# MBot.net
KiCad netlist of a schematic drawn in EAGLE
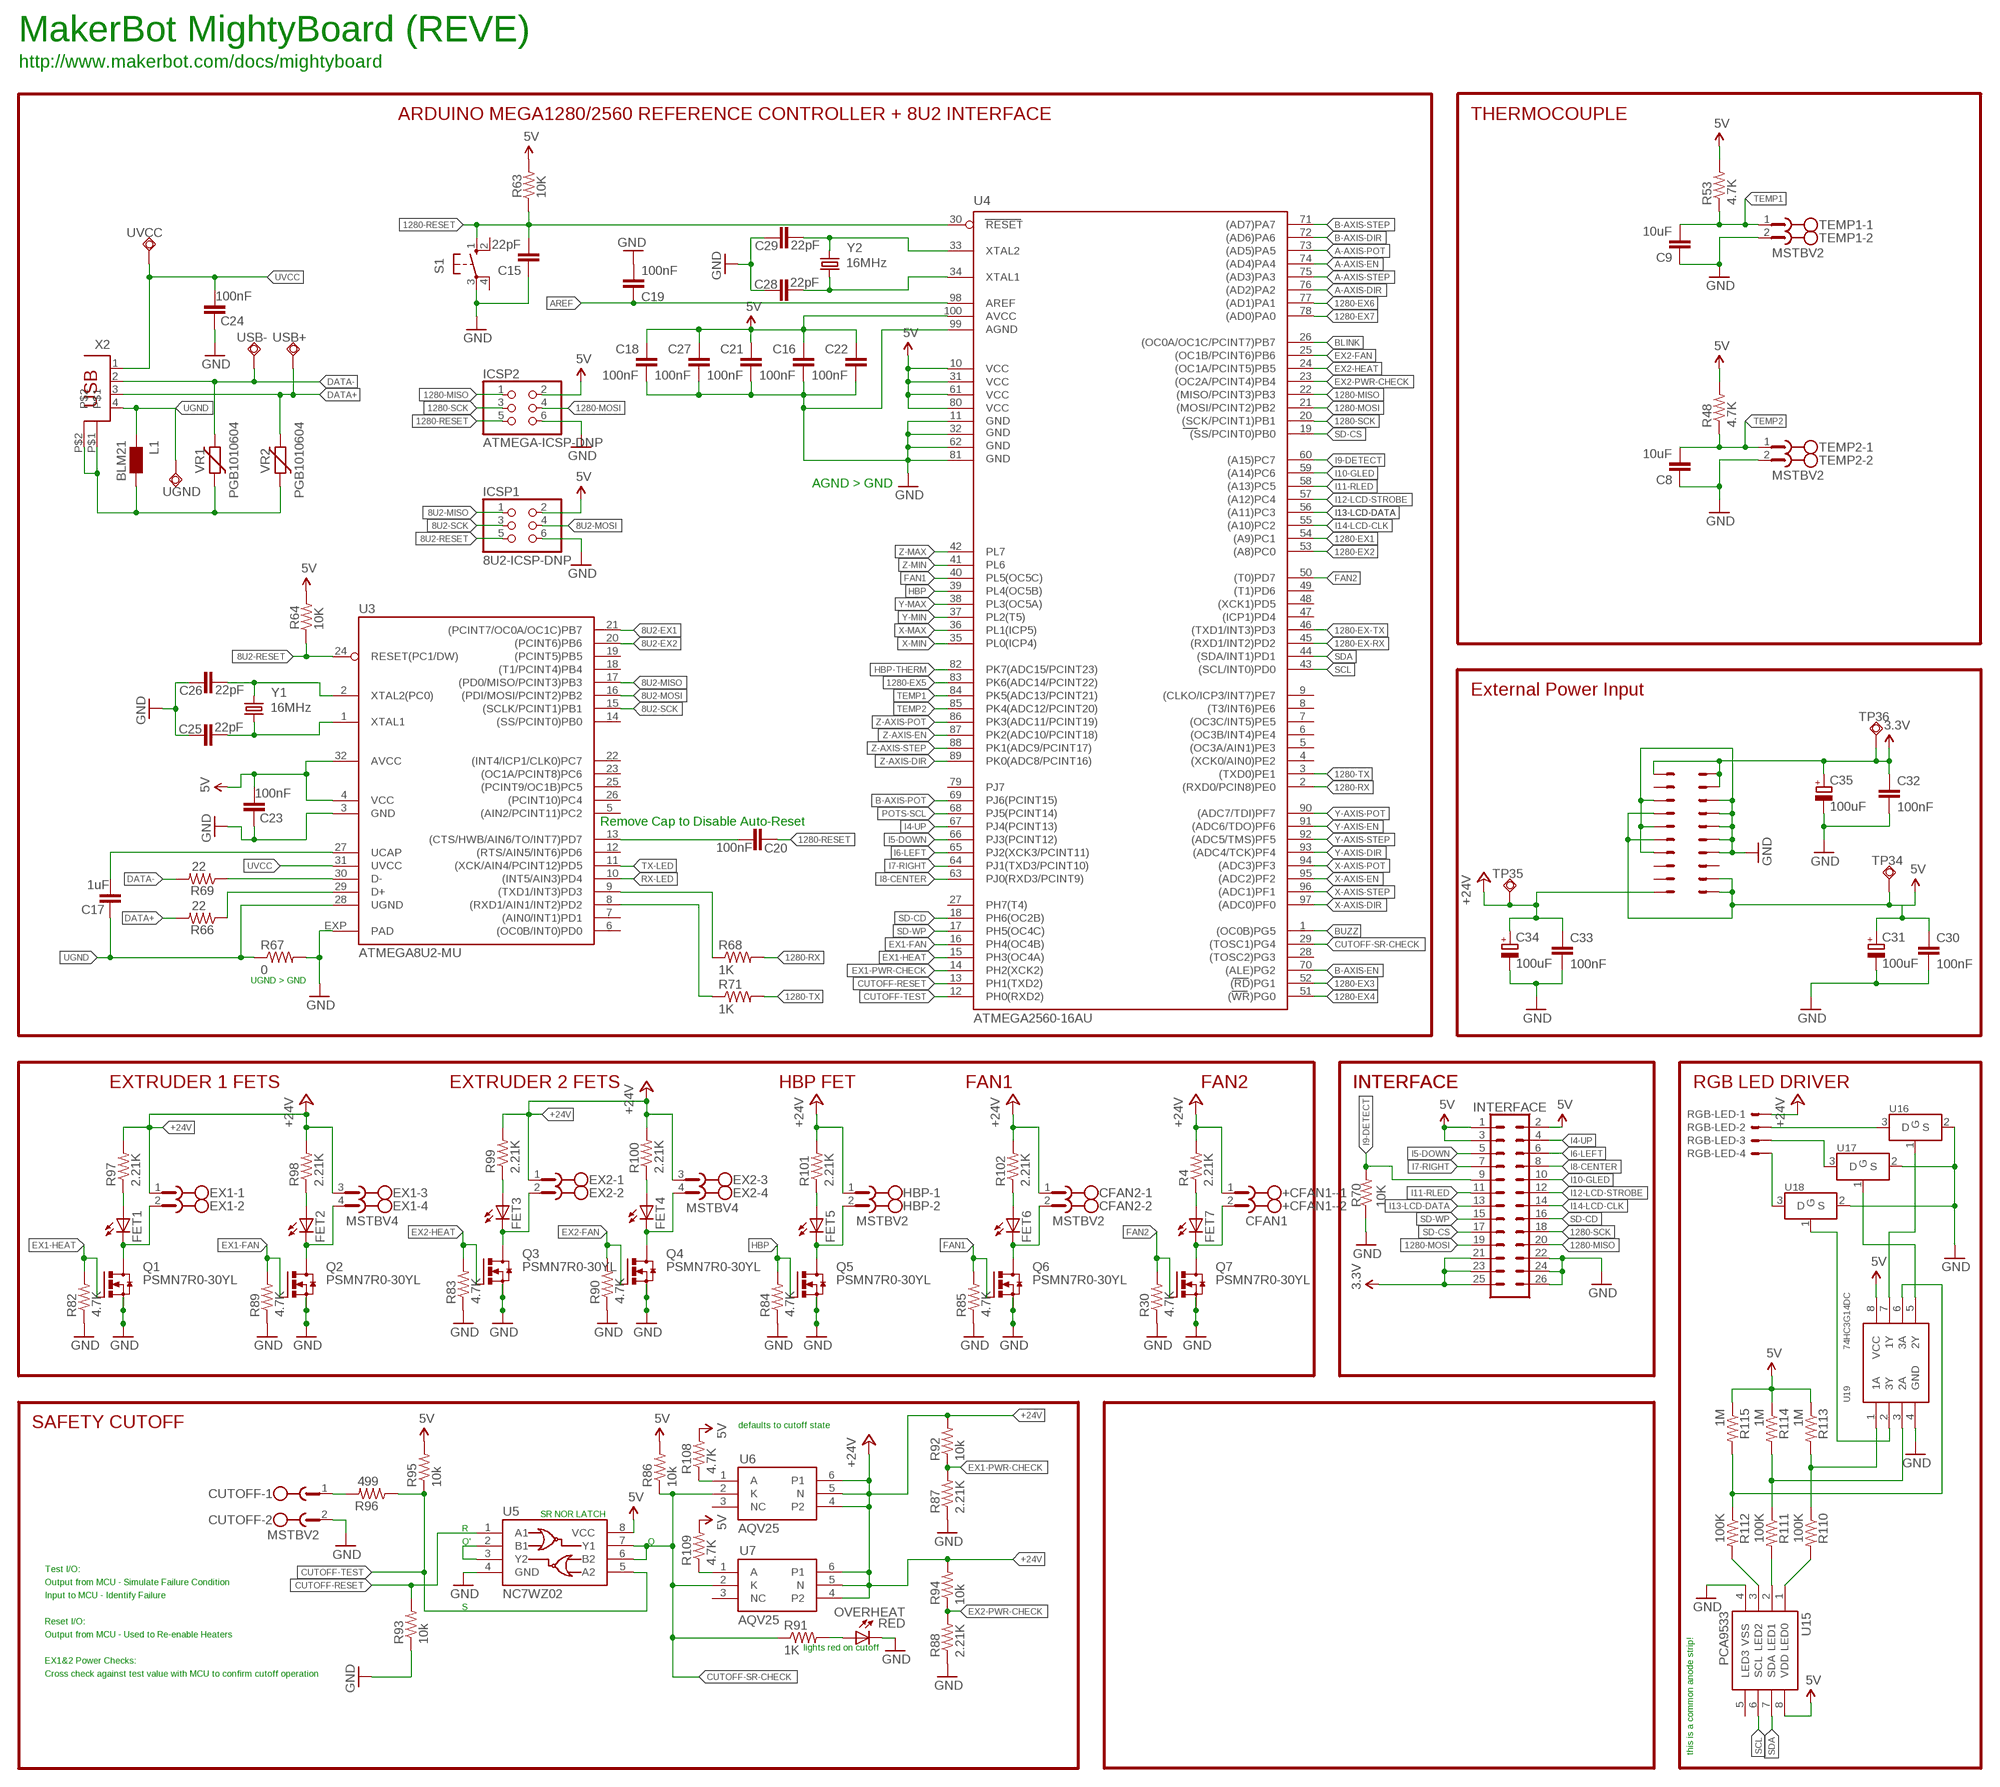
[diagram p0: schematic, sheet 1, part 1 of 2]
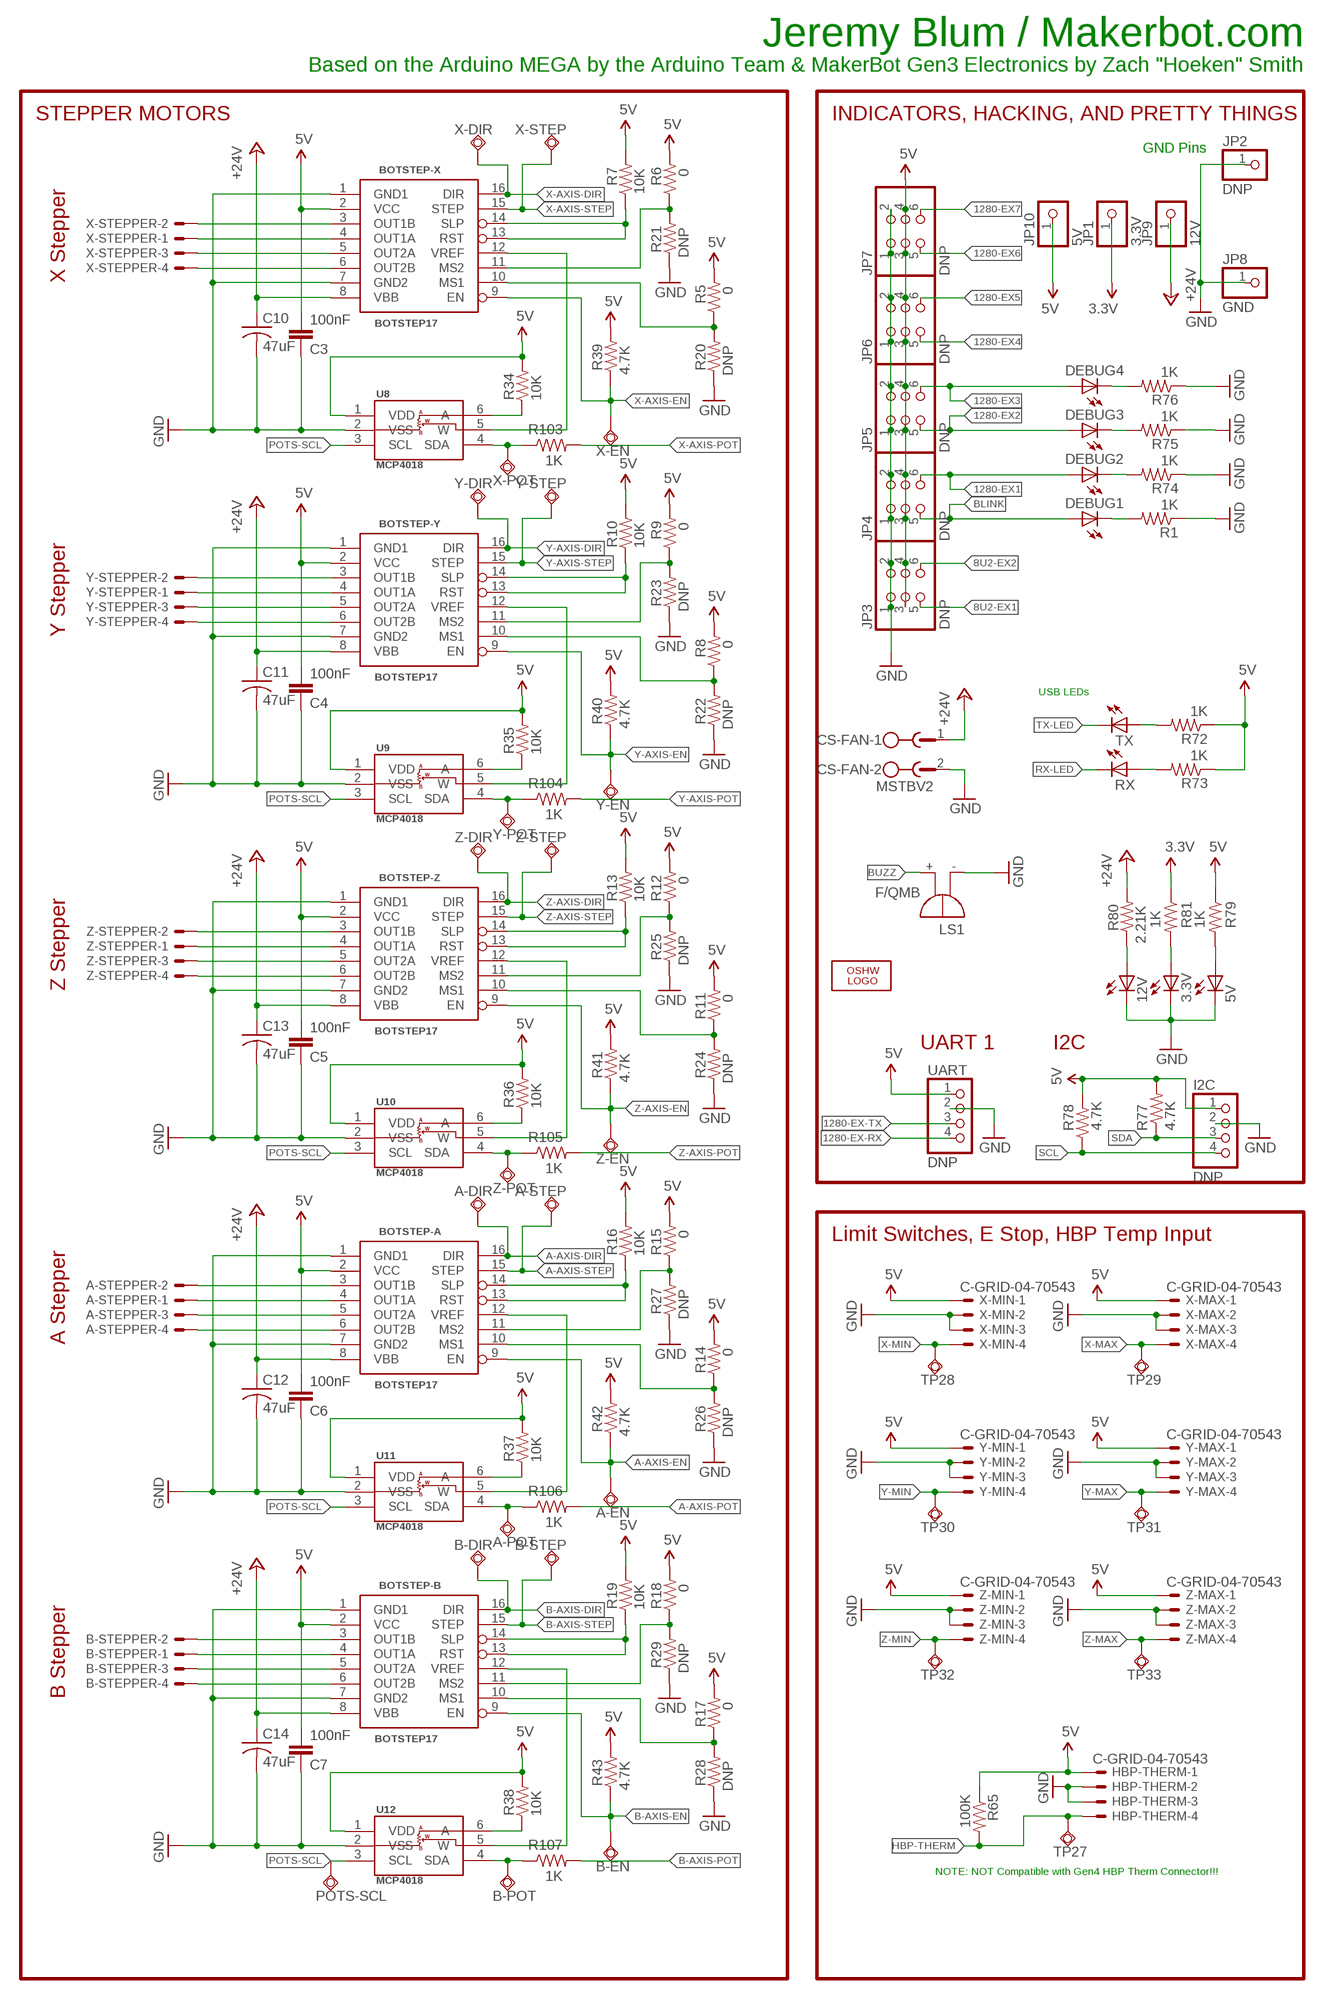
[diagram p1: schematic, sheet 1, part 2 of 2]

(export (version "E")
  (design (tool "Eeschema 10.0.6"))
  (components
    (comp (ref "+CFAN1-")
      (value "CFAN1")
      (footprint "eagle-import:MSTBV2")
      (fields (field (name "MPN") "MSTBV 2,5/2-GF-5.08"))
      (libsource (lib "eagle-import") (part "MSTBV2"))
    )
    (comp (ref "3.3V")
      (value "GREEN")
      (footprint "eagle-import:LED-0805")
      (libsource (lib "eagle-import") (part "LED0805"))
    )
    (comp (ref "5V")
      (value "GREEN")
      (footprint "eagle-import:LED-0805")
      (libsource (lib "eagle-import") (part "LED0805"))
    )
    (comp (ref "12V")
      (value "GREEN")
      (footprint "eagle-import:LED-0805")
      (libsource (lib "eagle-import") (part "LED0805"))
    )
    (comp (ref "A-DIR")
      (value "TPSQTP09R")
      (footprint "eagle-import:TP09R")
      (libsource (lib "eagle-import") (part "TPSQTP09R"))
    )
    (comp (ref "A-EN")
      (value "TPSQTP09R")
      (footprint "eagle-import:TP09R")
      (libsource (lib "eagle-import") (part "TPSQTP09R"))
    )
    (comp (ref "A-POT")
      (value "TPSQTP09R")
      (footprint "eagle-import:TP09R")
      (libsource (lib "eagle-import") (part "TPSQTP09R"))
    )
    (comp (ref "A-STEP")
      (value "TPSQTP09R")
      (footprint "eagle-import:TP09R")
      (libsource (lib "eagle-import") (part "TPSQTP09R"))
    )
    (comp (ref "A-STEPPER")
      (value "KK-156-4")
      (footprint "eagle-import:KK-156-4")
      (libsource (lib "eagle-import") (part "KK-156-4"))
    )
    (comp (ref "B-DIR")
      (value "TPSQTP09R")
      (footprint "eagle-import:TP09R")
      (libsource (lib "eagle-import") (part "TPSQTP09R"))
    )
    (comp (ref "B-EN")
      (value "TPSQTP09R")
      (footprint "eagle-import:TP09R")
      (libsource (lib "eagle-import") (part "TPSQTP09R"))
    )
    (comp (ref "B-POT")
      (value "TPSQTP09R")
      (footprint "eagle-import:TP09R")
      (libsource (lib "eagle-import") (part "TPSQTP09R"))
    )
    (comp (ref "B-STEP")
      (value "TPSQTP09R")
      (footprint "eagle-import:TP09R")
      (libsource (lib "eagle-import") (part "TPSQTP09R"))
    )
    (comp (ref "B-STEPPER")
      (value "KK-156-4")
      (footprint "eagle-import:KK-156-4")
      (libsource (lib "eagle-import") (part "KK-156-4"))
    )
    (comp (ref "BOTSTEP-A")
      (value "BOTSTEP17")
      (footprint "eagle-import:BOTSTEP17-INV")
      (libsource (lib "eagle-import") (part "BOTSTEP17CHIP-DOWN"))
    )
    (comp (ref "BOTSTEP-B")
      (value "BOTSTEP17")
      (footprint "eagle-import:BOTSTEP17-INV")
      (libsource (lib "eagle-import") (part "BOTSTEP17CHIP-DOWN"))
    )
    (comp (ref "BOTSTEP-X")
      (value "BOTSTEP17")
      (footprint "eagle-import:BOTSTEP17-INV")
      (libsource (lib "eagle-import") (part "BOTSTEP17CHIP-DOWN"))
    )
    (comp (ref "BOTSTEP-Y")
      (value "BOTSTEP17")
      (footprint "eagle-import:BOTSTEP17-INV")
      (libsource (lib "eagle-import") (part "BOTSTEP17CHIP-DOWN"))
    )
    (comp (ref "BOTSTEP-Z")
      (value "BOTSTEP17")
      (footprint "eagle-import:BOTSTEP17-INV")
      (libsource (lib "eagle-import") (part "BOTSTEP17CHIP-DOWN"))
    )
    (comp (ref "C3")
      (value "100nF")
      (footprint "eagle-import:0805")
      (libsource (lib "eagle-import") (part "CAP0805"))
    )
    (comp (ref "C4")
      (value "100nF")
      (footprint "eagle-import:0805")
      (libsource (lib "eagle-import") (part "CAP0805"))
    )
    (comp (ref "C5")
      (value "100nF")
      (footprint "eagle-import:0805")
      (libsource (lib "eagle-import") (part "CAP0805"))
    )
    (comp (ref "C6")
      (value "100nF")
      (footprint "eagle-import:0805")
      (libsource (lib "eagle-import") (part "CAP0805"))
    )
    (comp (ref "C7")
      (value "100nF")
      (footprint "eagle-import:0805")
      (libsource (lib "eagle-import") (part "CAP0805"))
    )
    (comp (ref "C8")
      (value "10uF")
      (footprint "eagle-import:0805")
      (libsource (lib "eagle-import") (part "CAP0805"))
    )
    (comp (ref "C9")
      (value "10uF")
      (footprint "eagle-import:0805")
      (libsource (lib "eagle-import") (part "CAP0805"))
    )
    (comp (ref "C10")
      (value "47uF")
      (footprint "eagle-import:CAP2917")
      (libsource (lib "eagle-import") (part "C-US"))
    )
    (comp (ref "C11")
      (value "47uF")
      (footprint "eagle-import:CAP2917")
      (libsource (lib "eagle-import") (part "C-US"))
    )
    (comp (ref "C12")
      (value "47uF")
      (footprint "eagle-import:CAP2917")
      (libsource (lib "eagle-import") (part "C-US"))
    )
    (comp (ref "C13")
      (value "47uF")
      (footprint "eagle-import:CAP2917")
      (libsource (lib "eagle-import") (part "C-US"))
    )
    (comp (ref "C14")
      (value "47uF")
      (footprint "eagle-import:CAP2917")
      (libsource (lib "eagle-import") (part "C-US"))
    )
    (comp (ref "C15")
      (value "22pF")
      (footprint "eagle-import:0805")
      (libsource (lib "eagle-import") (part "CAP0805"))
    )
    (comp (ref "C16")
      (value "100nF")
      (footprint "eagle-import:0805")
      (libsource (lib "eagle-import") (part "CAP0805"))
    )
    (comp (ref "C17")
      (value "1uF")
      (footprint "eagle-import:0805")
      (libsource (lib "eagle-import") (part "CAP0805"))
    )
    (comp (ref "C18")
      (value "100nF")
      (footprint "eagle-import:0805")
      (libsource (lib "eagle-import") (part "CAP0805"))
    )
    (comp (ref "C19")
      (value "100nF")
      (footprint "eagle-import:0805")
      (libsource (lib "eagle-import") (part "CAP0805"))
    )
    (comp (ref "C20")
      (value "100nF")
      (footprint "eagle-import:0805")
      (libsource (lib "eagle-import") (part "CAP0805"))
    )
    (comp (ref "C21")
      (value "100nF")
      (footprint "eagle-import:0805")
      (libsource (lib "eagle-import") (part "CAP0805"))
    )
    (comp (ref "C22")
      (value "100nF")
      (footprint "eagle-import:0805")
      (libsource (lib "eagle-import") (part "CAP0805"))
    )
    (comp (ref "C23")
      (value "100nF")
      (footprint "eagle-import:0805")
      (libsource (lib "eagle-import") (part "CAP0805"))
    )
    (comp (ref "C24")
      (value "100nF")
      (footprint "eagle-import:0805")
      (libsource (lib "eagle-import") (part "CAP0805"))
    )
    (comp (ref "C25")
      (value "22pF")
      (footprint "eagle-import:0805")
      (libsource (lib "eagle-import") (part "CAP0805"))
    )
    (comp (ref "C26")
      (value "22pF")
      (footprint "eagle-import:0805")
      (libsource (lib "eagle-import") (part "CAP0805"))
    )
    (comp (ref "C27")
      (value "100nF")
      (footprint "eagle-import:0805")
      (libsource (lib "eagle-import") (part "CAP0805"))
    )
    (comp (ref "C28")
      (value "22pF")
      (footprint "eagle-import:0805")
      (libsource (lib "eagle-import") (part "CAP0805"))
    )
    (comp (ref "C29")
      (value "22pF")
      (footprint "eagle-import:0805")
      (libsource (lib "eagle-import") (part "CAP0805"))
    )
    (comp (ref "C30")
      (value "100nF")
      (footprint "eagle-import:0805")
      (libsource (lib "eagle-import") (part "CAP0805"))
    )
    (comp (ref "C31")
      (value "100uF")
      (footprint "eagle-import:E3,5-8")
      (libsource (lib "eagle-import") (part "CPOL-EUE3.5-8"))
    )
    (comp (ref "C32")
      (value "100nF")
      (footprint "eagle-import:0805")
      (libsource (lib "eagle-import") (part "CAP0805"))
    )
    (comp (ref "C33")
      (value "100nF")
      (footprint "eagle-import:0805")
      (libsource (lib "eagle-import") (part "CAP0805"))
    )
    (comp (ref "C34")
      (value "100uF")
      (footprint "eagle-import:E3,5-8")
      (libsource (lib "eagle-import") (part "CPOL-EUE3.5-8"))
    )
    (comp (ref "C35")
      (value "100uF")
      (footprint "eagle-import:E3,5-8")
      (libsource (lib "eagle-import") (part "CPOL-EUE3.5-8"))
    )
    (comp (ref "CFAN2")
      (value "MSTBV2")
      (footprint "eagle-import:MSTBV2")
      (fields (field (name "MPN") "MSTBV 2,5/2-GF-5.08"))
      (libsource (lib "eagle-import") (part "MSTBV2"))
    )
    (comp (ref "CS-FAN")
      (value "MSTBV2")
      (footprint "eagle-import:MSTBV2")
      (fields (field (name "MPN") "MSTBV 2,5/2-GF-5.08"))
      (libsource (lib "eagle-import") (part "MSTBV2"))
    )
    (comp (ref "CUTOFF")
      (value "MSTBV2")
      (footprint "eagle-import:MSTBV2")
      (fields (field (name "MPN") "MSTBV 2,5/2-GF-5.08"))
      (libsource (lib "eagle-import") (part "MSTBV2"))
    )
    (comp (ref "DEBUG1")
      (value "GREEN")
      (footprint "eagle-import:LED-0805")
      (libsource (lib "eagle-import") (part "LED0805"))
    )
    (comp (ref "DEBUG2")
      (value "GREEN")
      (footprint "eagle-import:LED-0805")
      (libsource (lib "eagle-import") (part "LED0805"))
    )
    (comp (ref "DEBUG3")
      (value "GREEN")
      (footprint "eagle-import:LED-0805")
      (libsource (lib "eagle-import") (part "LED0805"))
    )
    (comp (ref "DEBUG4")
      (value "GREEN")
      (footprint "eagle-import:LED-0805")
      (libsource (lib "eagle-import") (part "LED0805"))
    )
    (comp (ref "EX1")
      (value "MSTBV4")
      (footprint "eagle-import:MSTBV4")
      (fields (field (name "MPN") "MSTBV 2,5/4-GF-5.08"))
      (libsource (lib "eagle-import") (part "MSTBV4"))
    )
    (comp (ref "EX2")
      (value "MSTBV4")
      (footprint "eagle-import:MSTBV4")
      (fields (field (name "MPN") "MSTBV 2,5/4-GF-5.08"))
      (libsource (lib "eagle-import") (part "MSTBV4"))
    )
    (comp (ref "FET1")
      (value "GREEN")
      (footprint "eagle-import:LED-0805")
      (libsource (lib "eagle-import") (part "LED0805"))
    )
    (comp (ref "FET2")
      (value "GREEN")
      (footprint "eagle-import:LED-0805")
      (libsource (lib "eagle-import") (part "LED0805"))
    )
    (comp (ref "FET3")
      (value "GREEN")
      (footprint "eagle-import:LED-0805")
      (libsource (lib "eagle-import") (part "LED0805"))
    )
    (comp (ref "FET4")
      (value "GREEN")
      (footprint "eagle-import:LED-0805")
      (libsource (lib "eagle-import") (part "LED0805"))
    )
    (comp (ref "FET5")
      (value "GREEN")
      (footprint "eagle-import:LED-0805")
      (libsource (lib "eagle-import") (part "LED0805"))
    )
    (comp (ref "FET6")
      (value "GREEN")
      (footprint "eagle-import:LED-0805")
      (libsource (lib "eagle-import") (part "LED0805"))
    )
    (comp (ref "FET7")
      (value "GREEN")
      (footprint "eagle-import:LED-0805")
      (libsource (lib "eagle-import") (part "LED0805"))
    )
    (comp (ref "HBP")
      (value "MSTBV2")
      (footprint "eagle-import:MSTBV2")
      (fields (field (name "MPN") "MSTBV 2,5/2-GF-5.08"))
      (libsource (lib "eagle-import") (part "MSTBV2"))
    )
    (comp (ref "HBP-THERM")
      (value "C-GRID-04-70543")
      (footprint "eagle-import:70543-04")
      (libsource (lib "eagle-import") (part "C-GRID-04-70543"))
    )
    (comp (ref "I2C")
      (value "DNP")
      (footprint "eagle-import:1X04")
      (libsource (lib "eagle-import") (part "PINHD-1X4"))
    )
    (comp (ref "ICSP1")
      (value "8U2-ICSP-DNP")
      (footprint "eagle-import:2X03")
      (libsource (lib "eagle-import") (part "PINHD-2X3"))
    )
    (comp (ref "ICSP2")
      (value "ATMEGA-ICSP-DNP")
      (footprint "eagle-import:2X03")
      (libsource (lib "eagle-import") (part "PINHD-2X3"))
    )
    (comp (ref "INTERFACE")
      (value "ML26")
      (footprint "eagle-import:ML26")
      (libsource (lib "eagle-import") (part "ML26"))
    )
    (comp (ref "JP1")
      (value "3.3V")
      (footprint "eagle-import:1X01")
      (libsource (lib "eagle-import") (part "PINHD-1X1"))
    )
    (comp (ref "JP2")
      (value "DNP")
      (footprint "eagle-import:1X01")
      (libsource (lib "eagle-import") (part "PINHD-1X1"))
    )
    (comp (ref "JP3")
      (value "DNP")
      (footprint "eagle-import:2X03")
      (libsource (lib "eagle-import") (part "PINHD-2X3"))
    )
    (comp (ref "JP4")
      (value "DNP")
      (footprint "eagle-import:2X03")
      (libsource (lib "eagle-import") (part "PINHD-2X3"))
    )
    (comp (ref "JP5")
      (value "DNP")
      (footprint "eagle-import:2X03")
      (libsource (lib "eagle-import") (part "PINHD-2X3"))
    )
    (comp (ref "JP6")
      (value "DNP")
      (footprint "eagle-import:2X03")
      (libsource (lib "eagle-import") (part "PINHD-2X3"))
    )
    (comp (ref "JP7")
      (value "DNP")
      (footprint "eagle-import:2X03")
      (libsource (lib "eagle-import") (part "PINHD-2X3"))
    )
    (comp (ref "JP8")
      (value "GND")
      (footprint "eagle-import:1X01")
      (libsource (lib "eagle-import") (part "PINHD-1X1"))
    )
    (comp (ref "JP9")
      (value "12V")
      (footprint "eagle-import:1X01")
      (libsource (lib "eagle-import") (part "PINHD-1X1"))
    )
    (comp (ref "JP10")
      (value "5V")
      (footprint "eagle-import:1X01")
      (libsource (lib "eagle-import") (part "PINHD-1X1"))
    )
    (comp (ref "L1")
      (value "BLM21")
      (footprint "eagle-import:0805")
      (libsource (lib "eagle-import") (part "WE-CBF_0805"))
    )
    (comp (ref "LOGO2")
      (value "OSHW_LOGO_10MILX0200-NT")
      (footprint "eagle-import:OSHW_10X200_NOTEXT")
      (libsource (lib "eagle-import") (part "OSHW_LOGO_10MILX0200-NT"))
    )
    (comp (ref "LS1")
      (value "F/QMB")
      (footprint "eagle-import:F_QMB")
      (libsource (lib "eagle-import") (part "F/QMB"))
    )
    (comp (ref "OVERHEAT")
      (value "RED")
      (footprint "eagle-import:LED-0805")
      (libsource (lib "eagle-import") (part "LED0805"))
    )
    (comp (ref "POTS-SCL")
      (value "TPSQTP09R")
      (footprint "eagle-import:TP09R")
      (libsource (lib "eagle-import") (part "TPSQTP09R"))
    )
    (comp (ref "Q1")
      (value "PSMN7R0-30YL")
      (footprint "eagle-import:SOT669")
      (libsource (lib "eagle-import") (part "PSMN7R0-30YL"))
    )
    (comp (ref "Q2")
      (value "PSMN7R0-30YL")
      (footprint "eagle-import:SOT669")
      (libsource (lib "eagle-import") (part "PSMN7R0-30YL"))
    )
    (comp (ref "Q3")
      (value "PSMN7R0-30YL")
      (footprint "eagle-import:SOT669")
      (libsource (lib "eagle-import") (part "PSMN7R0-30YL"))
    )
    (comp (ref "Q4")
      (value "PSMN7R0-30YL")
      (footprint "eagle-import:SOT669")
      (libsource (lib "eagle-import") (part "PSMN7R0-30YL"))
    )
    (comp (ref "Q5")
      (value "PSMN7R0-30YL")
      (footprint "eagle-import:SOT669")
      (libsource (lib "eagle-import") (part "PSMN7R0-30YL"))
    )
    (comp (ref "Q6")
      (value "PSMN7R0-30YL")
      (footprint "eagle-import:SOT669")
      (libsource (lib "eagle-import") (part "PSMN7R0-30YL"))
    )
    (comp (ref "Q7")
      (value "PSMN7R0-30YL")
      (footprint "eagle-import:SOT669")
      (libsource (lib "eagle-import") (part "PSMN7R0-30YL"))
    )
    (comp (ref "R1")
      (value "1K")
      (footprint "eagle-import:0805")
      (libsource (lib "eagle-import") (part "RESISTOR"))
    )
    (comp (ref "R4")
      (value "2.21K")
      (footprint "eagle-import:0805")
      (libsource (lib "eagle-import") (part "RESISTOR"))
    )
    (comp (ref "R5")
      (value "0")
      (footprint "eagle-import:0805")
      (libsource (lib "eagle-import") (part "RESISTOR"))
    )
    (comp (ref "R6")
      (value "0")
      (footprint "eagle-import:0805")
      (libsource (lib "eagle-import") (part "RESISTOR"))
    )
    (comp (ref "R7")
      (value "10K")
      (footprint "eagle-import:0805")
      (libsource (lib "eagle-import") (part "RESISTOR"))
    )
    (comp (ref "R8")
      (value "0")
      (footprint "eagle-import:0805")
      (libsource (lib "eagle-import") (part "RESISTOR"))
    )
    (comp (ref "R9")
      (value "0")
      (footprint "eagle-import:0805")
      (libsource (lib "eagle-import") (part "RESISTOR"))
    )
    (comp (ref "R10")
      (value "10K")
      (footprint "eagle-import:0805")
      (libsource (lib "eagle-import") (part "RESISTOR"))
    )
    (comp (ref "R11")
      (value "0")
      (footprint "eagle-import:0805")
      (libsource (lib "eagle-import") (part "RESISTOR"))
    )
    (comp (ref "R12")
      (value "0")
      (footprint "eagle-import:0805")
      (libsource (lib "eagle-import") (part "RESISTOR"))
    )
    (comp (ref "R13")
      (value "10K")
      (footprint "eagle-import:0805")
      (libsource (lib "eagle-import") (part "RESISTOR"))
    )
    (comp (ref "R14")
      (value "0")
      (footprint "eagle-import:0805")
      (libsource (lib "eagle-import") (part "RESISTOR"))
    )
    (comp (ref "R15")
      (value "0")
      (footprint "eagle-import:0805")
      (libsource (lib "eagle-import") (part "RESISTOR"))
    )
    (comp (ref "R16")
      (value "10K")
      (footprint "eagle-import:0805")
      (libsource (lib "eagle-import") (part "RESISTOR"))
    )
    (comp (ref "R17")
      (value "0")
      (footprint "eagle-import:0805")
      (libsource (lib "eagle-import") (part "RESISTOR"))
    )
    (comp (ref "R18")
      (value "0")
      (footprint "eagle-import:0805")
      (libsource (lib "eagle-import") (part "RESISTOR"))
    )
    (comp (ref "R19")
      (value "10K")
      (footprint "eagle-import:0805")
      (libsource (lib "eagle-import") (part "RESISTOR"))
    )
    (comp (ref "R20")
      (value "DNP")
      (footprint "eagle-import:0805")
      (libsource (lib "eagle-import") (part "RESISTOR"))
    )
    (comp (ref "R21")
      (value "DNP")
      (footprint "eagle-import:0805")
      (libsource (lib "eagle-import") (part "RESISTOR"))
    )
    (comp (ref "R22")
      (value "DNP")
      (footprint "eagle-import:0805")
      (libsource (lib "eagle-import") (part "RESISTOR"))
    )
    (comp (ref "R23")
      (value "DNP")
      (footprint "eagle-import:0805")
      (libsource (lib "eagle-import") (part "RESISTOR"))
    )
    (comp (ref "R24")
      (value "DNP")
      (footprint "eagle-import:0805")
      (libsource (lib "eagle-import") (part "RESISTOR"))
    )
    (comp (ref "R25")
      (value "DNP")
      (footprint "eagle-import:0805")
      (libsource (lib "eagle-import") (part "RESISTOR"))
    )
    (comp (ref "R26")
      (value "DNP")
      (footprint "eagle-import:0805")
      (libsource (lib "eagle-import") (part "RESISTOR"))
    )
    (comp (ref "R27")
      (value "DNP")
      (footprint "eagle-import:0805")
      (libsource (lib "eagle-import") (part "RESISTOR"))
    )
    (comp (ref "R28")
      (value "DNP")
      (footprint "eagle-import:0805")
      (libsource (lib "eagle-import") (part "RESISTOR"))
    )
    (comp (ref "R29")
      (value "DNP")
      (footprint "eagle-import:0805")
      (libsource (lib "eagle-import") (part "RESISTOR"))
    )
    (comp (ref "R30")
      (value "4.7K")
      (footprint "eagle-import:0805")
      (libsource (lib "eagle-import") (part "RESISTOR"))
    )
    (comp (ref "R34")
      (value "10K")
      (footprint "eagle-import:0805")
      (libsource (lib "eagle-import") (part "RESISTOR"))
    )
    (comp (ref "R35")
      (value "10K")
      (footprint "eagle-import:0805")
      (libsource (lib "eagle-import") (part "RESISTOR"))
    )
    (comp (ref "R36")
      (value "10K")
      (footprint "eagle-import:0805")
      (libsource (lib "eagle-import") (part "RESISTOR"))
    )
    (comp (ref "R37")
      (value "10K")
      (footprint "eagle-import:0805")
      (libsource (lib "eagle-import") (part "RESISTOR"))
    )
    (comp (ref "R38")
      (value "10K")
      (footprint "eagle-import:0805")
      (libsource (lib "eagle-import") (part "RESISTOR"))
    )
    (comp (ref "R39")
      (value "4.7K")
      (footprint "eagle-import:0805")
      (libsource (lib "eagle-import") (part "RESISTOR"))
    )
    (comp (ref "R40")
      (value "4.7K")
      (footprint "eagle-import:0805")
      (libsource (lib "eagle-import") (part "RESISTOR"))
    )
    (comp (ref "R41")
      (value "4.7K")
      (footprint "eagle-import:0805")
      (libsource (lib "eagle-import") (part "RESISTOR"))
    )
    (comp (ref "R42")
      (value "4.7K")
      (footprint "eagle-import:0805")
      (libsource (lib "eagle-import") (part "RESISTOR"))
    )
    (comp (ref "R43")
      (value "4.7K")
      (footprint "eagle-import:0805")
      (libsource (lib "eagle-import") (part "RESISTOR"))
    )
    (comp (ref "R48")
      (value "4.7K")
      (footprint "eagle-import:0805")
      (libsource (lib "eagle-import") (part "RESISTOR"))
    )
    (comp (ref "R53")
      (value "4.7K")
      (footprint "eagle-import:0805")
      (libsource (lib "eagle-import") (part "RESISTOR"))
    )
    (comp (ref "R63")
      (value "10K")
      (footprint "eagle-import:0805")
      (libsource (lib "eagle-import") (part "RESISTOR"))
    )
    (comp (ref "R64")
      (value "10K")
      (footprint "eagle-import:0805")
      (libsource (lib "eagle-import") (part "RESISTOR"))
    )
    (comp (ref "R65")
      (value "100K")
      (footprint "eagle-import:0805")
      (libsource (lib "eagle-import") (part "RESISTOR"))
    )
    (comp (ref "R66")
      (value "22")
      (footprint "eagle-import:0805")
      (libsource (lib "eagle-import") (part "RESISTOR"))
    )
    (comp (ref "R67")
      (value "0")
      (footprint "eagle-import:0805")
      (libsource (lib "eagle-import") (part "RESISTOR"))
    )
    (comp (ref "R68")
      (value "1K")
      (footprint "eagle-import:0805")
      (libsource (lib "eagle-import") (part "RESISTOR"))
    )
    (comp (ref "R69")
      (value "22")
      (footprint "eagle-import:0805")
      (libsource (lib "eagle-import") (part "RESISTOR"))
    )
    (comp (ref "R70")
      (value "10K")
      (footprint "eagle-import:0805")
      (libsource (lib "eagle-import") (part "RESISTOR"))
    )
    (comp (ref "R71")
      (value "1K")
      (footprint "eagle-import:0805")
      (libsource (lib "eagle-import") (part "RESISTOR"))
    )
    (comp (ref "R72")
      (value "1K")
      (footprint "eagle-import:0805")
      (libsource (lib "eagle-import") (part "RESISTOR"))
    )
    (comp (ref "R73")
      (value "1K")
      (footprint "eagle-import:0805")
      (libsource (lib "eagle-import") (part "RESISTOR"))
    )
    (comp (ref "R74")
      (value "1K")
      (footprint "eagle-import:0805")
      (libsource (lib "eagle-import") (part "RESISTOR"))
    )
    (comp (ref "R75")
      (value "1K")
      (footprint "eagle-import:0805")
      (libsource (lib "eagle-import") (part "RESISTOR"))
    )
    (comp (ref "R76")
      (value "1K")
      (footprint "eagle-import:0805")
      (libsource (lib "eagle-import") (part "RESISTOR"))
    )
    (comp (ref "R77")
      (value "4.7K")
      (footprint "eagle-import:0805")
      (libsource (lib "eagle-import") (part "RESISTOR"))
    )
    (comp (ref "R78")
      (value "4.7K")
      (footprint "eagle-import:0805")
      (libsource (lib "eagle-import") (part "RESISTOR"))
    )
    (comp (ref "R79")
      (value "1K")
      (footprint "eagle-import:0805")
      (libsource (lib "eagle-import") (part "RESISTOR"))
    )
    (comp (ref "R80")
      (value "2.21K")
      (footprint "eagle-import:0805")
      (libsource (lib "eagle-import") (part "RESISTOR"))
    )
    (comp (ref "R81")
      (value "1K")
      (footprint "eagle-import:0805")
      (libsource (lib "eagle-import") (part "RESISTOR"))
    )
    (comp (ref "R82")
      (value "4.7K")
      (footprint "eagle-import:0805")
      (libsource (lib "eagle-import") (part "RESISTOR"))
    )
    (comp (ref "R83")
      (value "4.7K")
      (footprint "eagle-import:0805")
      (libsource (lib "eagle-import") (part "RESISTOR"))
    )
    (comp (ref "R84")
      (value "4.7K")
      (footprint "eagle-import:0805")
      (libsource (lib "eagle-import") (part "RESISTOR"))
    )
    (comp (ref "R85")
      (value "4.7K")
      (footprint "eagle-import:0805")
      (libsource (lib "eagle-import") (part "RESISTOR"))
    )
    (comp (ref "R86")
      (value "10k")
      (footprint "eagle-import:0805")
      (libsource (lib "eagle-import") (part "RESISTOR"))
    )
    (comp (ref "R87")
      (value "2.21K")
      (footprint "eagle-import:0805")
      (libsource (lib "eagle-import") (part "RESISTOR"))
    )
    (comp (ref "R88")
      (value "2.21K")
      (footprint "eagle-import:0805")
      (libsource (lib "eagle-import") (part "RESISTOR"))
    )
    (comp (ref "R89")
      (value "4.7K")
      (footprint "eagle-import:0805")
      (libsource (lib "eagle-import") (part "RESISTOR"))
    )
    (comp (ref "R90")
      (value "4.7K")
      (footprint "eagle-import:0805")
      (libsource (lib "eagle-import") (part "RESISTOR"))
    )
    (comp (ref "R91")
      (value "1K")
      (footprint "eagle-import:0805")
      (libsource (lib "eagle-import") (part "RESISTOR"))
    )
    (comp (ref "R92")
      (value "10k")
      (footprint "eagle-import:0805")
      (libsource (lib "eagle-import") (part "RESISTOR"))
    )
    (comp (ref "R93")
      (value "10k")
      (footprint "eagle-import:0805")
      (libsource (lib "eagle-import") (part "RESISTOR"))
    )
    (comp (ref "R94")
      (value "10k")
      (footprint "eagle-import:0805")
      (libsource (lib "eagle-import") (part "RESISTOR"))
    )
    (comp (ref "R95")
      (value "10k")
      (footprint "eagle-import:0805")
      (libsource (lib "eagle-import") (part "RESISTOR"))
    )
    (comp (ref "R96")
      (value "499")
      (footprint "eagle-import:0805")
      (libsource (lib "eagle-import") (part "RESISTOR"))
    )
    (comp (ref "R97")
      (value "2.21K")
      (footprint "eagle-import:0805")
      (libsource (lib "eagle-import") (part "RESISTOR"))
    )
    (comp (ref "R98")
      (value "2.21K")
      (footprint "eagle-import:0805")
      (libsource (lib "eagle-import") (part "RESISTOR"))
    )
    (comp (ref "R99")
      (value "2.21K")
      (footprint "eagle-import:0805")
      (libsource (lib "eagle-import") (part "RESISTOR"))
    )
    (comp (ref "R100")
      (value "2.21K")
      (footprint "eagle-import:0805")
      (libsource (lib "eagle-import") (part "RESISTOR"))
    )
    (comp (ref "R101")
      (value "2.21K")
      (footprint "eagle-import:0805")
      (libsource (lib "eagle-import") (part "RESISTOR"))
    )
    (comp (ref "R102")
      (value "2.21K")
      (footprint "eagle-import:0805")
      (libsource (lib "eagle-import") (part "RESISTOR"))
    )
    (comp (ref "R103")
      (value "1K")
      (footprint "eagle-import:0805")
      (libsource (lib "eagle-import") (part "RESISTOR"))
    )
    (comp (ref "R104")
      (value "1K")
      (footprint "eagle-import:0805")
      (libsource (lib "eagle-import") (part "RESISTOR"))
    )
    (comp (ref "R105")
      (value "1K")
      (footprint "eagle-import:0805")
      (libsource (lib "eagle-import") (part "RESISTOR"))
    )
    (comp (ref "R106")
      (value "1K")
      (footprint "eagle-import:0805")
      (libsource (lib "eagle-import") (part "RESISTOR"))
    )
    (comp (ref "R107")
      (value "1K")
      (footprint "eagle-import:0805")
      (libsource (lib "eagle-import") (part "RESISTOR"))
    )
    (comp (ref "R108")
      (value "4.7K")
      (footprint "eagle-import:0805")
      (libsource (lib "eagle-import") (part "RESISTOR"))
    )
    (comp (ref "R109")
      (value "4.7K")
      (footprint "eagle-import:0805")
      (libsource (lib "eagle-import") (part "RESISTOR"))
    )
    (comp (ref "R110")
      (value "100K")
      (footprint "eagle-import:0805")
      (libsource (lib "eagle-import") (part "RESISTOR"))
    )
    (comp (ref "R111")
      (value "100K")
      (footprint "eagle-import:0805")
      (libsource (lib "eagle-import") (part "RESISTOR"))
    )
    (comp (ref "R112")
      (value "100K")
      (footprint "eagle-import:0805")
      (libsource (lib "eagle-import") (part "RESISTOR"))
    )
    (comp (ref "R113")
      (value "1M")
      (footprint "eagle-import:0805")
      (libsource (lib "eagle-import") (part "RESISTOR"))
    )
    (comp (ref "R114")
      (value "1M")
      (footprint "eagle-import:0805")
      (libsource (lib "eagle-import") (part "RESISTOR"))
    )
    (comp (ref "R115")
      (value "1M")
      (footprint "eagle-import:0805")
      (libsource (lib "eagle-import") (part "RESISTOR"))
    )
    (comp (ref "RGB-LED")
      (value "C-GRID-04-70543")
      (footprint "eagle-import:70543-04")
      (libsource (lib "eagle-import") (part "C-GRID-04-70543"))
    )
    (comp (ref "RX")
      (value "GREEN")
      (footprint "eagle-import:LED-0805")
      (libsource (lib "eagle-import") (part "LED0805"))
    )
    (comp (ref "S1")
      (value "10-XX")
      (footprint "eagle-import:B3F-10XX")
      (fields (field (name "MPN") "B3F-1000"))
      (libsource (lib "eagle-import") (part "10-XX"))
    )
    (comp (ref "TEMP1")
      (value "MSTBV2")
      (footprint "eagle-import:MSTBV2")
      (fields
        (field (name "MPN") "MSTBV 2,5/2-GF-5.08")
        (field (name "MPN_1") "MSTBV 2,5/2-GF-5.08")
        (field (name "OC_FARNELL") "1792792")
        (field (name "OC_NEWARK") "69R9845")
      )
      (libsource (lib "eagle-import") (part "MSTBV2"))
    )
    (comp (ref "TEMP2")
      (value "MSTBV2")
      (footprint "eagle-import:MSTBV2")
      (fields
        (field (name "MPN") "MSTBV 2,5/2-GF-5.08")
        (field (name "MPN_1") "MSTBV 2,5/2-GF-5.08")
        (field (name "OC_FARNELL") "1792792")
        (field (name "OC_NEWARK") "69R9845")
      )
      (libsource (lib "eagle-import") (part "MSTBV2"))
    )
    (comp (ref "TP27")
      (value "TPSQTP09R")
      (footprint "eagle-import:TP09R")
      (libsource (lib "eagle-import") (part "TPSQTP09R"))
    )
    (comp (ref "TP28")
      (value "TPSQTP09R")
      (footprint "eagle-import:TP09R")
      (libsource (lib "eagle-import") (part "TPSQTP09R"))
    )
    (comp (ref "TP29")
      (value "TPSQTP09R")
      (footprint "eagle-import:TP09R")
      (libsource (lib "eagle-import") (part "TPSQTP09R"))
    )
    (comp (ref "TP30")
      (value "TPSQTP09R")
      (footprint "eagle-import:TP09R")
      (libsource (lib "eagle-import") (part "TPSQTP09R"))
    )
    (comp (ref "TP31")
      (value "TPSQTP09R")
      (footprint "eagle-import:TP09R")
      (libsource (lib "eagle-import") (part "TPSQTP09R"))
    )
    (comp (ref "TP32")
      (value "TPSQTP09R")
      (footprint "eagle-import:TP09R")
      (libsource (lib "eagle-import") (part "TPSQTP09R"))
    )
    (comp (ref "TP33")
      (value "TPSQTP09R")
      (footprint "eagle-import:TP09R")
      (libsource (lib "eagle-import") (part "TPSQTP09R"))
    )
    (comp (ref "TP34")
      (value "TPSQTP09R")
      (footprint "eagle-import:TP09R")
      (libsource (lib "eagle-import") (part "TPSQTP09R"))
    )
    (comp (ref "TP35")
      (value "TPSQTP09R")
      (footprint "eagle-import:TP09R")
      (libsource (lib "eagle-import") (part "TPSQTP09R"))
    )
    (comp (ref "TP36")
      (value "TPSQTP09R")
      (footprint "eagle-import:TP09R")
      (libsource (lib "eagle-import") (part "TPSQTP09R"))
    )
    (comp (ref "TX")
      (value "GREEN")
      (footprint "eagle-import:LED-0805")
      (libsource (lib "eagle-import") (part "LED0805"))
    )
    (comp (ref "U3")
      (value "ATMEGA8U2-MU")
      (footprint "eagle-import:QFN32")
      (libsource (lib "eagle-import") (part "ATMEGA8U2-MU"))
    )
    (comp (ref "U4")
      (value "ATMEGA2560-16AU")
      (footprint "eagle-import:TQFP100")
      (libsource (lib "eagle-import") (part "ATMEGAAU1280-16"))
    )
    (comp (ref "U5")
      (value "NC7WZ02")
      (footprint "eagle-import:US8")
      (libsource (lib "eagle-import") (part "NC7WZ02"))
    )
    (comp (ref "U6")
      (value "AQV25")
      (footprint "eagle-import:AQV25-DIPSM")
      (libsource (lib "eagle-import") (part "AQV25EXISTS"))
    )
    (comp (ref "U7")
      (value "AQV25")
      (footprint "eagle-import:AQV25-DIPSM")
      (libsource (lib "eagle-import") (part "AQV25EXISTS"))
    )
    (comp (ref "U8")
      (value "MCP4018")
      (footprint "eagle-import:SC70-6L")
      (libsource (lib "eagle-import") (part "MCP4018"))
    )
    (comp (ref "U9")
      (value "MCP4018")
      (footprint "eagle-import:SC70-6L")
      (libsource (lib "eagle-import") (part "MCP4018"))
    )
    (comp (ref "U10")
      (value "MCP4018")
      (footprint "eagle-import:SC70-6L")
      (libsource (lib "eagle-import") (part "MCP4018"))
    )
    (comp (ref "U11")
      (value "MCP4018")
      (footprint "eagle-import:SC70-6L")
      (libsource (lib "eagle-import") (part "MCP4018"))
    )
    (comp (ref "U12")
      (value "MCP4018")
      (footprint "eagle-import:SC70-6L")
      (libsource (lib "eagle-import") (part "MCP4018"))
    )
    (comp (ref "U15")
      (value "PCA9533")
      (footprint "eagle-import:SO8")
      (libsource (lib "eagle-import") (part "PCA9533"))
    )
    (comp (ref "U16")
      (value "FDV301N")
      (footprint "eagle-import:SOT-23")
      (libsource (lib "eagle-import") (part "FDV301N"))
    )
    (comp (ref "U17")
      (value "FDV301N")
      (footprint "eagle-import:SOT-23")
      (libsource (lib "eagle-import") (part "FDV301N"))
    )
    (comp (ref "U18")
      (value "FDV301N")
      (footprint "eagle-import:SOT-23")
      (libsource (lib "eagle-import") (part "FDV301N"))
    )
    (comp (ref "U19")
      (value "74HC3G14DC")
      (footprint "eagle-import:VSSOP8")
      (libsource (lib "eagle-import") (part "74HC3G14DC"))
    )
    (comp (ref "UART")
      (value "DNP")
      (footprint "eagle-import:1X04")
      (libsource (lib "eagle-import") (part "PINHD-1X4"))
    )
    (comp (ref "UGND")
      (value "TPSQTP09R")
      (footprint "eagle-import:TP09R")
      (libsource (lib "eagle-import") (part "TPSQTP09R"))
    )
    (comp (ref "USB+")
      (value "TPSQTP09R")
      (footprint "eagle-import:TP09R")
      (libsource (lib "eagle-import") (part "TPSQTP09R"))
    )
    (comp (ref "USB-")
      (value "TPSQTP09R")
      (footprint "eagle-import:TP09R")
      (libsource (lib "eagle-import") (part "TPSQTP09R"))
    )
    (comp (ref "UVCC")
      (value "TPSQTP09R")
      (footprint "eagle-import:TP09R")
      (libsource (lib "eagle-import") (part "TPSQTP09R"))
    )
    (comp (ref "VR1")
      (value "PGB1010604")
      (footprint "eagle-import:CT_CN0603")
      (libsource (lib "eagle-import") (part "VARISTORCN0603"))
    )
    (comp (ref "VR2")
      (value "PGB1010604")
      (footprint "eagle-import:CT_CN0603")
      (libsource (lib "eagle-import") (part "VARISTORCN0603"))
    )
    (comp (ref "X-DIR")
      (value "TPSQTP09R")
      (footprint "eagle-import:TP09R")
      (libsource (lib "eagle-import") (part "TPSQTP09R"))
    )
    (comp (ref "X-EN")
      (value "TPSQTP09R")
      (footprint "eagle-import:TP09R")
      (libsource (lib "eagle-import") (part "TPSQTP09R"))
    )
    (comp (ref "X-MAX")
      (value "C-GRID-04-70543")
      (footprint "eagle-import:70543-04")
      (libsource (lib "eagle-import") (part "C-GRID-04-70543"))
    )
    (comp (ref "X-MIN")
      (value "C-GRID-04-70543")
      (footprint "eagle-import:70543-04")
      (libsource (lib "eagle-import") (part "C-GRID-04-70543"))
    )
    (comp (ref "X-POT")
      (value "TPSQTP09R")
      (footprint "eagle-import:TP09R")
      (libsource (lib "eagle-import") (part "TPSQTP09R"))
    )
    (comp (ref "X-STEP")
      (value "TPSQTP09R")
      (footprint "eagle-import:TP09R")
      (libsource (lib "eagle-import") (part "TPSQTP09R"))
    )
    (comp (ref "X-STEPPER")
      (value "KK-156-4")
      (footprint "eagle-import:KK-156-4")
      (libsource (lib "eagle-import") (part "KK-156-4"))
    )
    (comp (ref "X2")
      (value "USBA")
      (footprint "eagle-import:SMARTPRJ_PN61729")
      (libsource (lib "eagle-import") (part "USBA"))
    )
    (comp (ref "X3")
      (value "5569")
      (footprint "eagle-import:5569")
      (libsource (lib "eagle-import") (part "5569"))
    )
    (comp (ref "Y-DIR")
      (value "TPSQTP09R")
      (footprint "eagle-import:TP09R")
      (libsource (lib "eagle-import") (part "TPSQTP09R"))
    )
    (comp (ref "Y-EN")
      (value "TPSQTP09R")
      (footprint "eagle-import:TP09R")
      (libsource (lib "eagle-import") (part "TPSQTP09R"))
    )
    (comp (ref "Y-MAX")
      (value "C-GRID-04-70543")
      (footprint "eagle-import:70543-04")
      (libsource (lib "eagle-import") (part "C-GRID-04-70543"))
    )
    (comp (ref "Y-MIN")
      (value "C-GRID-04-70543")
      (footprint "eagle-import:70543-04")
      (libsource (lib "eagle-import") (part "C-GRID-04-70543"))
    )
    (comp (ref "Y-POT")
      (value "TPSQTP09R")
      (footprint "eagle-import:TP09R")
      (libsource (lib "eagle-import") (part "TPSQTP09R"))
    )
    (comp (ref "Y-STEP")
      (value "TPSQTP09R")
      (footprint "eagle-import:TP09R")
      (libsource (lib "eagle-import") (part "TPSQTP09R"))
    )
    (comp (ref "Y-STEPPER")
      (value "KK-156-4")
      (footprint "eagle-import:KK-156-4")
      (libsource (lib "eagle-import") (part "KK-156-4"))
    )
    (comp (ref "Y1")
      (value "16MHz")
      (footprint "eagle-import:HC49_S")
      (libsource (lib "eagle-import") (part "CRYTALHC49S"))
    )
    (comp (ref "Y2")
      (value "16MHz")
      (footprint "eagle-import:HC49_S")
      (libsource (lib "eagle-import") (part "CRYTALHC49S"))
    )
    (comp (ref "Z-DIR")
      (value "TPSQTP09R")
      (footprint "eagle-import:TP09R")
      (libsource (lib "eagle-import") (part "TPSQTP09R"))
    )
    (comp (ref "Z-EN")
      (value "TPSQTP09R")
      (footprint "eagle-import:TP09R")
      (libsource (lib "eagle-import") (part "TPSQTP09R"))
    )
    (comp (ref "Z-MAX")
      (value "C-GRID-04-70543")
      (footprint "eagle-import:70543-04")
      (libsource (lib "eagle-import") (part "C-GRID-04-70543"))
    )
    (comp (ref "Z-MIN")
      (value "C-GRID-04-70543")
      (footprint "eagle-import:70543-04")
      (libsource (lib "eagle-import") (part "C-GRID-04-70543"))
    )
    (comp (ref "Z-POT")
      (value "TPSQTP09R")
      (footprint "eagle-import:TP09R")
      (libsource (lib "eagle-import") (part "TPSQTP09R"))
    )
    (comp (ref "Z-STEP")
      (value "TPSQTP09R")
      (footprint "eagle-import:TP09R")
      (libsource (lib "eagle-import") (part "TPSQTP09R"))
    )
    (comp (ref "Z-STEPPER")
      (value "KK-156-4")
      (footprint "eagle-import:KK-156-4")
      (libsource (lib "eagle-import") (part "KK-156-4"))
    )
  )
  (nets
    (net (code "1") (name "+24V") (class "Default")
      (node (ref "+CFAN1-") (pin "1") (pinfunction "1_1") (pintype "passive"))
      (node (ref "BOTSTEP-A") (pin "8") (pinfunction "VBB_8") (pintype "bidirectional"))
      (node (ref "BOTSTEP-B") (pin "8") (pinfunction "VBB_8") (pintype "bidirectional"))
      (node (ref "BOTSTEP-X") (pin "8") (pinfunction "VBB_8") (pintype "bidirectional"))
      (node (ref "BOTSTEP-Y") (pin "8") (pinfunction "VBB_8") (pintype "bidirectional"))
      (node (ref "BOTSTEP-Z") (pin "8") (pinfunction "VBB_8") (pintype "bidirectional"))
      (node (ref "C10") (pin "1") (pinfunction "1_1") (pintype "passive"))
      (node (ref "C11") (pin "1") (pinfunction "1_1") (pintype "passive"))
      (node (ref "C12") (pin "1") (pinfunction "1_1") (pintype "passive"))
      (node (ref "C13") (pin "1") (pinfunction "1_1") (pintype "passive"))
      (node (ref "C14") (pin "1") (pinfunction "1_1") (pintype "passive"))
      (node (ref "C33") (pin "1") (pinfunction "1_1") (pintype "passive"))
      (node (ref "C34") (pin "+") (pinfunction "+_+") (pintype "passive"))
      (node (ref "CFAN2") (pin "1") (pinfunction "1_1") (pintype "passive"))
      (node (ref "CS-FAN") (pin "1") (pinfunction "1_1") (pintype "passive"))
      (node (ref "EX1") (pin "1") (pinfunction "1_1") (pintype "passive"))
      (node (ref "EX1") (pin "3") (pinfunction "1_3") (pintype "passive"))
      (node (ref "EX2") (pin "1") (pinfunction "1_1") (pintype "passive"))
      (node (ref "EX2") (pin "3") (pinfunction "1_3") (pintype "passive"))
      (node (ref "HBP") (pin "1") (pinfunction "1_1") (pintype "passive"))
      (node (ref "JP9") (pin "1") (pinfunction "1_1") (pintype "passive"))
      (node (ref "R100") (pin "2") (pinfunction "2_2") (pintype "passive"))
      (node (ref "R101") (pin "2") (pinfunction "2_2") (pintype "passive"))
      (node (ref "R102") (pin "2") (pinfunction "2_2") (pintype "passive"))
      (node (ref "R4") (pin "2") (pinfunction "2_2") (pintype "passive"))
      (node (ref "R80") (pin "2") (pinfunction "2_2") (pintype "passive"))
      (node (ref "R92") (pin "2") (pinfunction "2_2") (pintype "passive"))
      (node (ref "R94") (pin "2") (pinfunction "2_2") (pintype "passive"))
      (node (ref "R97") (pin "2") (pinfunction "2_2") (pintype "passive"))
      (node (ref "R98") (pin "2") (pinfunction "2_2") (pintype "passive"))
      (node (ref "R99") (pin "2") (pinfunction "2_2") (pintype "passive"))
      (node (ref "RGB-LED") (pin "1") (pinfunction "S_1") (pintype "passive"))
      (node (ref "TP35") (pin "TP") (pinfunction "TP_TP") (pintype "input"))
      (node (ref "U6") (pin "4") (pinfunction "P2_4") (pintype "bidirectional"))
      (node (ref "U6") (pin "5") (pinfunction "N_5") (pintype "bidirectional"))
      (node (ref "U6") (pin "6") (pinfunction "P1_6") (pintype "bidirectional"))
      (node (ref "U7") (pin "4") (pinfunction "P2_4") (pintype "bidirectional"))
      (node (ref "U7") (pin "5") (pinfunction "N_5") (pintype "bidirectional"))
      (node (ref "U7") (pin "6") (pinfunction "P1_6") (pintype "bidirectional"))
      (node (ref "X3") (pin "19") (pinfunction "19_19") (pintype "passive"))
    )
    (net (code "2") (name "3.3V") (class "Default")
      (node (ref "C32") (pin "1") (pinfunction "1_1") (pintype "passive"))
      (node (ref "C35") (pin "+") (pinfunction "+_+") (pintype "passive"))
      (node (ref "INTERFACE") (pin "21") (pinfunction "21_21") (pintype "passive"))
      (node (ref "INTERFACE") (pin "23") (pinfunction "23_23") (pintype "passive"))
      (node (ref "INTERFACE") (pin "25") (pinfunction "25_25") (pintype "passive"))
      (node (ref "JP1") (pin "1") (pinfunction "1_1") (pintype "passive"))
      (node (ref "R81") (pin "1") (pinfunction "1_1") (pintype "passive"))
      (node (ref "TP36") (pin "TP") (pinfunction "TP_TP") (pintype "input"))
      (node (ref "X3") (pin "1") (pinfunction "1_1") (pintype "passive"))
      (node (ref "X3") (pin "2") (pinfunction "2_2") (pintype "passive"))
      (node (ref "X3") (pin "4") (pinfunction "4_4") (pintype "passive"))
    )
    (net (code "3") (name "5V") (class "Default")
      (node (ref "BOTSTEP-A") (pin "2") (pinfunction "VCC_2") (pintype "bidirectional"))
      (node (ref "BOTSTEP-B") (pin "2") (pinfunction "VCC_2") (pintype "bidirectional"))
      (node (ref "BOTSTEP-X") (pin "2") (pinfunction "VCC_2") (pintype "bidirectional"))
      (node (ref "BOTSTEP-Y") (pin "2") (pinfunction "VCC_2") (pintype "bidirectional"))
      (node (ref "BOTSTEP-Z") (pin "2") (pinfunction "VCC_2") (pintype "bidirectional"))
      (node (ref "C16") (pin "1") (pinfunction "1_1") (pintype "passive"))
      (node (ref "C18") (pin "1") (pinfunction "1_1") (pintype "passive"))
      (node (ref "C21") (pin "1") (pinfunction "1_1") (pintype "passive"))
      (node (ref "C22") (pin "1") (pinfunction "1_1") (pintype "passive"))
      (node (ref "C23") (pin "2") (pinfunction "2_2") (pintype "passive"))
      (node (ref "C27") (pin "1") (pinfunction "1_1") (pintype "passive"))
      (node (ref "C3") (pin "2") (pinfunction "2_2") (pintype "passive"))
      (node (ref "C30") (pin "1") (pinfunction "1_1") (pintype "passive"))
      (node (ref "C31") (pin "+") (pinfunction "+_+") (pintype "passive"))
      (node (ref "C4") (pin "2") (pinfunction "2_2") (pintype "passive"))
      (node (ref "C5") (pin "2") (pinfunction "2_2") (pintype "passive"))
      (node (ref "C6") (pin "2") (pinfunction "2_2") (pintype "passive"))
      (node (ref "C7") (pin "2") (pinfunction "2_2") (pintype "passive"))
      (node (ref "HBP-THERM") (pin "1") (pinfunction "S_1") (pintype "passive"))
      (node (ref "I2C") (pin "1") (pinfunction "1_1") (pintype "passive"))
      (node (ref "ICSP1") (pin "2") (pinfunction "2_2") (pintype "passive"))
      (node (ref "ICSP2") (pin "2") (pinfunction "2_2") (pintype "passive"))
      (node (ref "INTERFACE") (pin "1") (pinfunction "1_1") (pintype "passive"))
      (node (ref "INTERFACE") (pin "2") (pinfunction "2_2") (pintype "passive"))
      (node (ref "INTERFACE") (pin "3") (pinfunction "3_3") (pintype "passive"))
      (node (ref "JP10") (pin "1") (pinfunction "1_1") (pintype "passive"))
      (node (ref "JP3") (pin "3") (pinfunction "3_3") (pintype "passive"))
      (node (ref "JP3") (pin "4") (pinfunction "4_4") (pintype "passive"))
      (node (ref "JP4") (pin "3") (pinfunction "3_3") (pintype "passive"))
      (node (ref "JP4") (pin "4") (pinfunction "4_4") (pintype "passive"))
      (node (ref "JP5") (pin "3") (pinfunction "3_3") (pintype "passive"))
      (node (ref "JP5") (pin "4") (pinfunction "4_4") (pintype "passive"))
      (node (ref "JP6") (pin "3") (pinfunction "3_3") (pintype "passive"))
      (node (ref "JP6") (pin "4") (pinfunction "4_4") (pintype "passive"))
      (node (ref "JP7") (pin "3") (pinfunction "3_3") (pintype "passive"))
      (node (ref "JP7") (pin "4") (pinfunction "4_4") (pintype "passive"))
      (node (ref "R10") (pin "2") (pinfunction "2_2") (pintype "passive"))
      (node (ref "R108") (pin "2") (pinfunction "2_2") (pintype "passive"))
      (node (ref "R109") (pin "2") (pinfunction "2_2") (pintype "passive"))
      (node (ref "R11") (pin "2") (pinfunction "2_2") (pintype "passive"))
      (node (ref "R113") (pin "1") (pinfunction "1_1") (pintype "passive"))
      (node (ref "R114") (pin "1") (pinfunction "1_1") (pintype "passive"))
      (node (ref "R115") (pin "1") (pinfunction "1_1") (pintype "passive"))
      (node (ref "R12") (pin "2") (pinfunction "2_2") (pintype "passive"))
      (node (ref "R13") (pin "2") (pinfunction "2_2") (pintype "passive"))
      (node (ref "R14") (pin "2") (pinfunction "2_2") (pintype "passive"))
      (node (ref "R15") (pin "2") (pinfunction "2_2") (pintype "passive"))
      (node (ref "R16") (pin "2") (pinfunction "2_2") (pintype "passive"))
      (node (ref "R17") (pin "2") (pinfunction "2_2") (pintype "passive"))
      (node (ref "R18") (pin "2") (pinfunction "2_2") (pintype "passive"))
      (node (ref "R19") (pin "2") (pinfunction "2_2") (pintype "passive"))
      (node (ref "R34") (pin "2") (pinfunction "2_2") (pintype "passive"))
      (node (ref "R35") (pin "2") (pinfunction "2_2") (pintype "passive"))
      (node (ref "R36") (pin "2") (pinfunction "2_2") (pintype "passive"))
      (node (ref "R37") (pin "2") (pinfunction "2_2") (pintype "passive"))
      (node (ref "R38") (pin "2") (pinfunction "2_2") (pintype "passive"))
      (node (ref "R39") (pin "2") (pinfunction "2_2") (pintype "passive"))
      (node (ref "R40") (pin "2") (pinfunction "2_2") (pintype "passive"))
      (node (ref "R41") (pin "2") (pinfunction "2_2") (pintype "passive"))
      (node (ref "R42") (pin "2") (pinfunction "2_2") (pintype "passive"))
      (node (ref "R43") (pin "2") (pinfunction "2_2") (pintype "passive"))
      (node (ref "R48") (pin "2") (pinfunction "2_2") (pintype "passive"))
      (node (ref "R5") (pin "2") (pinfunction "2_2") (pintype "passive"))
      (node (ref "R53") (pin "2") (pinfunction "2_2") (pintype "passive"))
      (node (ref "R6") (pin "2") (pinfunction "2_2") (pintype "passive"))
      (node (ref "R63") (pin "2") (pinfunction "2_2") (pintype "passive"))
      (node (ref "R64") (pin "2") (pinfunction "2_2") (pintype "passive"))
      (node (ref "R65") (pin "1") (pinfunction "1_1") (pintype "passive"))
      (node (ref "R7") (pin "2") (pinfunction "2_2") (pintype "passive"))
      (node (ref "R72") (pin "1") (pinfunction "1_1") (pintype "passive"))
      (node (ref "R73") (pin "1") (pinfunction "1_1") (pintype "passive"))
      (node (ref "R77") (pin "2") (pinfunction "2_2") (pintype "passive"))
      (node (ref "R78") (pin "2") (pinfunction "2_2") (pintype "passive"))
      (node (ref "R79") (pin "1") (pinfunction "1_1") (pintype "passive"))
      (node (ref "R8") (pin "2") (pinfunction "2_2") (pintype "passive"))
      (node (ref "R86") (pin "2") (pinfunction "2_2") (pintype "passive"))
      (node (ref "R9") (pin "2") (pinfunction "2_2") (pintype "passive"))
      (node (ref "R95") (pin "2") (pinfunction "2_2") (pintype "passive"))
      (node (ref "TP34") (pin "TP") (pinfunction "TP_TP") (pintype "input"))
      (node (ref "U10") (pin "1") (pinfunction "VDD_1") (pintype "bidirectional"))
      (node (ref "U11") (pin "1") (pinfunction "VDD_1") (pintype "bidirectional"))
      (node (ref "U12") (pin "1") (pinfunction "VDD_1") (pintype "bidirectional"))
      (node (ref "U15") (pin "8") (pinfunction "VDD_8") (pintype "bidirectional"))
      (node (ref "U19") (pin "8") (pinfunction "VCC_8") (pintype "bidirectional"))
      (node (ref "U3") (pin "32") (pinfunction "AVCC_32") (pintype "power_in"))
      (node (ref "U3") (pin "4") (pinfunction "VCC_4") (pintype "power_in"))
      (node (ref "U4") (pin "10") (pinfunction "VCC_10") (pintype "power_in"))
      (node (ref "U4") (pin "100") (pinfunction "AVCC_100") (pintype "power_in"))
      (node (ref "U4") (pin "31") (pinfunction "VCC1_31") (pintype "power_in"))
      (node (ref "U4") (pin "61") (pinfunction "VCC2_61") (pintype "power_in"))
      (node (ref "U4") (pin "80") (pinfunction "VCC3_80") (pintype "power_in"))
      (node (ref "U5") (pin "8") (pinfunction "VCC_8") (pintype "bidirectional"))
      (node (ref "U8") (pin "1") (pinfunction "VDD_1") (pintype "bidirectional"))
      (node (ref "U9") (pin "1") (pinfunction "VDD_1") (pintype "bidirectional"))
      (node (ref "UART") (pin "1") (pinfunction "1_1") (pintype "passive"))
      (node (ref "X-MAX") (pin "1") (pinfunction "S_1") (pintype "passive"))
      (node (ref "X-MIN") (pin "1") (pinfunction "S_1") (pintype "passive"))
      (node (ref "X3") (pin "11") (pinfunction "11_11") (pintype "passive"))
      (node (ref "X3") (pin "18") (pinfunction "18_18") (pintype "passive"))
      (node (ref "X3") (pin "20") (pinfunction "20_20") (pintype "passive"))
      (node (ref "X3") (pin "7") (pinfunction "7_7") (pintype "passive"))
      (node (ref "Y-MAX") (pin "1") (pinfunction "S_1") (pintype "passive"))
      (node (ref "Y-MIN") (pin "1") (pinfunction "S_1") (pintype "passive"))
      (node (ref "Z-MAX") (pin "1") (pinfunction "S_1") (pintype "passive"))
      (node (ref "Z-MIN") (pin "1") (pinfunction "S_1") (pintype "passive"))
    )
    (net (code "4") (name "8U2-EX1") (class "Default")
      (node (ref "JP3") (pin "5") (pinfunction "5_5") (pintype "passive"))
      (node (ref "U3") (pin "21") (pinfunction "(PCINT7/OC0A/OC1C)PB7_21") (pintype "bidirectional"))
    )
    (net (code "5") (name "8U2-EX2") (class "Default")
      (node (ref "JP3") (pin "6") (pinfunction "6_6") (pintype "passive"))
      (node (ref "U3") (pin "20") (pinfunction "(PCINT6)PB6_20") (pintype "bidirectional"))
    )
    (net (code "6") (name "8U2-MISO") (class "Default")
      (node (ref "ICSP1") (pin "1") (pinfunction "1_1") (pintype "passive"))
      (node (ref "U3") (pin "17") (pinfunction "(PD0/MISO/PCINT3)PB3_17") (pintype "bidirectional"))
    )
    (net (code "7") (name "8U2-MOSI") (class "Default")
      (node (ref "ICSP1") (pin "4") (pinfunction "4_4") (pintype "passive"))
      (node (ref "U3") (pin "16") (pinfunction "(PDI/MOSI/PCINT2)PB2_16") (pintype "bidirectional"))
    )
    (net (code "8") (name "8U2-RESET") (class "Default")
      (node (ref "ICSP1") (pin "5") (pinfunction "5_5") (pintype "passive"))
      (node (ref "R64") (pin "1") (pinfunction "1_1") (pintype "passive"))
      (node (ref "U3") (pin "24") (pinfunction "RESET(PC1/DW)_24") (pintype "input"))
    )
    (net (code "9") (name "8U2-SCK") (class "Default")
      (node (ref "ICSP1") (pin "3") (pinfunction "3_3") (pintype "passive"))
      (node (ref "U3") (pin "15") (pinfunction "(SCLK/PCINT1)PB1_15") (pintype "bidirectional"))
    )
    (net (code "10") (name "1280-EX-RX") (class "Default")
      (node (ref "U4") (pin "45") (pinfunction "(RXD1/INT2)PD2_45") (pintype "bidirectional"))
      (node (ref "UART") (pin "4") (pinfunction "4_4") (pintype "passive"))
    )
    (net (code "11") (name "1280-EX-TX") (class "Default")
      (node (ref "U4") (pin "46") (pinfunction "(TXD1/INT3)PD3_46") (pintype "bidirectional"))
      (node (ref "UART") (pin "3") (pinfunction "3_3") (pintype "passive"))
    )
    (net (code "12") (name "1280-EX1") (class "Default")
      (node (ref "DEBUG2") (pin "A") (pinfunction "A_A") (pintype "passive"))
      (node (ref "JP4") (pin "6") (pinfunction "6_6") (pintype "passive"))
      (node (ref "U4") (pin "54") (pinfunction "(A9)PC1_54") (pintype "bidirectional"))
    )
    (net (code "13") (name "1280-EX2") (class "Default")
      (node (ref "DEBUG3") (pin "A") (pinfunction "A_A") (pintype "passive"))
      (node (ref "JP5") (pin "5") (pinfunction "5_5") (pintype "passive"))
      (node (ref "U4") (pin "53") (pinfunction "(A8)PC0_53") (pintype "bidirectional"))
    )
    (net (code "14") (name "1280-EX3") (class "Default")
      (node (ref "DEBUG4") (pin "A") (pinfunction "A_A") (pintype "passive"))
      (node (ref "JP5") (pin "6") (pinfunction "6_6") (pintype "passive"))
      (node (ref "U4") (pin "52") (pinfunction "(RD)PG1_52") (pintype "bidirectional"))
    )
    (net (code "15") (name "1280-EX4") (class "Default")
      (node (ref "JP6") (pin "5") (pinfunction "5_5") (pintype "passive"))
      (node (ref "U4") (pin "51") (pinfunction "(WR)PG0_51") (pintype "bidirectional"))
    )
    (net (code "16") (name "1280-EX5") (class "Default")
      (node (ref "JP6") (pin "6") (pinfunction "6_6") (pintype "passive"))
      (node (ref "U4") (pin "83") (pinfunction "PK6(ADC14/PCINT22)_83") (pintype "bidirectional"))
    )
    (net (code "17") (name "1280-EX6") (class "Default")
      (node (ref "JP7") (pin "5") (pinfunction "5_5") (pintype "passive"))
      (node (ref "U4") (pin "77") (pinfunction "(AD1)PA1_77") (pintype "bidirectional"))
    )
    (net (code "18") (name "1280-EX7") (class "Default")
      (node (ref "JP7") (pin "6") (pinfunction "6_6") (pintype "passive"))
      (node (ref "U4") (pin "78") (pinfunction "(AD0)PA0_78") (pintype "bidirectional"))
    )
    (net (code "19") (name "1280-MISO") (class "Default")
      (node (ref "ICSP2") (pin "1") (pinfunction "1_1") (pintype "passive"))
      (node (ref "INTERFACE") (pin "20") (pinfunction "20_20") (pintype "passive"))
      (node (ref "U4") (pin "22") (pinfunction "(MISO/PCINT3)PB3_22") (pintype "bidirectional"))
    )
    (net (code "20") (name "1280-MOSI") (class "Default")
      (node (ref "ICSP2") (pin "4") (pinfunction "4_4") (pintype "passive"))
      (node (ref "INTERFACE") (pin "19") (pinfunction "19_19") (pintype "passive"))
      (node (ref "U4") (pin "21") (pinfunction "(MOSI/PCINT2)PB2_21") (pintype "bidirectional"))
    )
    (net (code "21") (name "1280-RESET") (class "Default")
      (node (ref "C15") (pin "2") (pinfunction "2_2") (pintype "passive"))
      (node (ref "C20") (pin "1") (pinfunction "1_1") (pintype "passive"))
      (node (ref "ICSP2") (pin "5") (pinfunction "5_5") (pintype "passive"))
      (node (ref "R63") (pin "1") (pinfunction "1_1") (pintype "passive"))
      (node (ref "S1") (pin "1") (pinfunction "S_1") (pintype "passive"))
      (node (ref "U4") (pin "30") (pinfunction "RESET_30") (pintype "input"))
    )
    (net (code "22") (name "1280-RX") (class "Default")
      (node (ref "R68") (pin "2") (pinfunction "2_2") (pintype "passive"))
      (node (ref "U4") (pin "2") (pinfunction "(RXD0/PCIN8)PE0_2") (pintype "bidirectional"))
    )
    (net (code "23") (name "1280-SCK") (class "Default")
      (node (ref "ICSP2") (pin "3") (pinfunction "3_3") (pintype "passive"))
      (node (ref "INTERFACE") (pin "18") (pinfunction "18_18") (pintype "passive"))
      (node (ref "U4") (pin "20") (pinfunction "(SCK/PCINT1)PB1_20") (pintype "bidirectional"))
    )
    (net (code "24") (name "1280-TX") (class "Default")
      (node (ref "R71") (pin "2") (pinfunction "2_2") (pintype "passive"))
      (node (ref "U4") (pin "3") (pinfunction "(TXD0)PE1_3") (pintype "bidirectional"))
    )
    (net (code "25") (name "A-AXIS-DIR") (class "Default")
      (node (ref "A-DIR") (pin "TP") (pinfunction "TP_TP") (pintype "input"))
      (node (ref "BOTSTEP-A") (pin "16") (pinfunction "DIR_16") (pintype "input"))
      (node (ref "U4") (pin "76") (pinfunction "(AD2)PA2_76") (pintype "bidirectional"))
    )
    (net (code "26") (name "A-AXIS-EN") (class "Default")
      (node (ref "A-EN") (pin "TP") (pinfunction "TP_TP") (pintype "input"))
      (node (ref "BOTSTEP-A") (pin "9") (pinfunction "EN_9") (pintype "input"))
      (node (ref "R42") (pin "1") (pinfunction "1_1") (pintype "passive"))
      (node (ref "U4") (pin "74") (pinfunction "(AD4)PA4_74") (pintype "bidirectional"))
    )
    (net (code "27") (name "A-AXIS-POT") (class "Default")
      (node (ref "R106") (pin "2") (pinfunction "2_2") (pintype "passive"))
      (node (ref "U4") (pin "73") (pinfunction "(AD5)PA5_73") (pintype "bidirectional"))
    )
    (net (code "28") (name "A-AXIS-STEP") (class "Default")
      (node (ref "A-STEP") (pin "TP") (pinfunction "TP_TP") (pintype "input"))
      (node (ref "BOTSTEP-A") (pin "15") (pinfunction "STEP_15") (pintype "input"))
      (node (ref "U4") (pin "75") (pinfunction "(AD3)PA3_75") (pintype "bidirectional"))
    )
    (net (code "29") (name "AREF") (class "Default")
      (node (ref "C19") (pin "1") (pinfunction "1_1") (pintype "passive"))
      (node (ref "U4") (pin "98") (pinfunction "AREF_98") (pintype "bidirectional"))
    )
    (net (code "30") (name "B-AXIS-DIR") (class "Default")
      (node (ref "B-DIR") (pin "TP") (pinfunction "TP_TP") (pintype "input"))
      (node (ref "BOTSTEP-B") (pin "16") (pinfunction "DIR_16") (pintype "input"))
      (node (ref "U4") (pin "72") (pinfunction "(AD6)PA6_72") (pintype "bidirectional"))
    )
    (net (code "31") (name "B-AXIS-EN") (class "Default")
      (node (ref "B-EN") (pin "TP") (pinfunction "TP_TP") (pintype "input"))
      (node (ref "BOTSTEP-B") (pin "9") (pinfunction "EN_9") (pintype "input"))
      (node (ref "R43") (pin "1") (pinfunction "1_1") (pintype "passive"))
      (node (ref "U4") (pin "70") (pinfunction "(ALE)PG2_70") (pintype "bidirectional"))
    )
    (net (code "32") (name "B-AXIS-POT") (class "Default")
      (node (ref "R107") (pin "2") (pinfunction "2_2") (pintype "passive"))
      (node (ref "U4") (pin "69") (pinfunction "PJ6(PCINT15)_69") (pintype "bidirectional"))
    )
    (net (code "33") (name "B-AXIS-STEP") (class "Default")
      (node (ref "B-STEP") (pin "TP") (pinfunction "TP_TP") (pintype "input"))
      (node (ref "BOTSTEP-B") (pin "15") (pinfunction "STEP_15") (pintype "input"))
      (node (ref "U4") (pin "71") (pinfunction "(AD7)PA7_71") (pintype "bidirectional"))
    )
    (net (code "34") (name "BLINK") (class "Default")
      (node (ref "DEBUG1") (pin "A") (pinfunction "A_A") (pintype "passive"))
      (node (ref "JP4") (pin "5") (pinfunction "5_5") (pintype "passive"))
      (node (ref "U4") (pin "26") (pinfunction "(OC0A/OC1C/PCINT7)PB7_26") (pintype "bidirectional"))
    )
    (net (code "35") (name "BUZZ") (class "Default")
      (node (ref "LS1") (pin "+") (pinfunction "-_+") (pintype "passive"))
      (node (ref "U4") (pin "1") (pinfunction "(OC0B)PG5_1") (pintype "bidirectional"))
    )
    (net (code "36") (name "CUTOFF-RESET") (class "Default")
      (node (ref "R93") (pin "2") (pinfunction "2_2") (pintype "passive"))
      (node (ref "U4") (pin "13") (pinfunction "PH1(TXD2)_13") (pintype "bidirectional"))
      (node (ref "U5") (pin "1") (pinfunction "A1_1") (pintype "bidirectional"))
    )
    (net (code "37") (name "CUTOFF-SR-CHECK") (class "Default")
      (node (ref "R86") (pin "1") (pinfunction "1_1") (pintype "passive"))
      (node (ref "R91") (pin "1") (pinfunction "1_1") (pintype "passive"))
      (node (ref "U4") (pin "29") (pinfunction "(TOSC1)PG4_29") (pintype "bidirectional"))
      (node (ref "U5") (pin "6") (pinfunction "B2_6") (pintype "bidirectional"))
      (node (ref "U5") (pin "7") (pinfunction "Y1_7") (pintype "bidirectional"))
      (node (ref "U6") (pin "2") (pinfunction "K_2") (pintype "bidirectional"))
      (node (ref "U7") (pin "2") (pinfunction "K_2") (pintype "bidirectional"))
    )
    (net (code "38") (name "CUTOFF-TEST") (class "Default")
      (node (ref "R95") (pin "1") (pinfunction "1_1") (pintype "passive"))
      (node (ref "R96") (pin "1") (pinfunction "1_1") (pintype "passive"))
      (node (ref "U4") (pin "12") (pinfunction "PH0(RXD2)_12") (pintype "bidirectional"))
      (node (ref "U5") (pin "5") (pinfunction "A2_5") (pintype "bidirectional"))
    )
    (net (code "39") (name "DATA+") (class "Default")
      (node (ref "R66") (pin "2") (pinfunction "2_2") (pintype "passive"))
      (node (ref "USB+") (pin "TP") (pinfunction "TP_TP") (pintype "input"))
      (node (ref "VR2") (pin "2") (pinfunction "2_2") (pintype "passive"))
      (node (ref "X2") (pin "3") (pinfunction "3_3") (pintype "bidirectional"))
    )
    (net (code "40") (name "DATA-") (class "Default")
      (node (ref "R69") (pin "2") (pinfunction "2_2") (pintype "passive"))
      (node (ref "USB-") (pin "TP") (pinfunction "TP_TP") (pintype "input"))
      (node (ref "VR1") (pin "2") (pinfunction "2_2") (pintype "passive"))
      (node (ref "X2") (pin "2") (pinfunction "2_2") (pintype "bidirectional"))
    )
    (net (code "41") (name "EX1-FAN") (class "Default")
      (node (ref "Q2") (pin "4") (pinfunction "G_4") (pintype "passive"))
      (node (ref "R89") (pin "2") (pinfunction "2_2") (pintype "passive"))
      (node (ref "U4") (pin "16") (pinfunction "PH4(OC4B)_16") (pintype "bidirectional"))
    )
    (net (code "42") (name "EX1-HEAT") (class "Default")
      (node (ref "Q1") (pin "4") (pinfunction "G_4") (pintype "passive"))
      (node (ref "R82") (pin "2") (pinfunction "2_2") (pintype "passive"))
      (node (ref "U4") (pin "15") (pinfunction "PH3(OC4A)_15") (pintype "bidirectional"))
    )
    (net (code "43") (name "EX1-PWR-CHECK") (class "Default")
      (node (ref "R87") (pin "2") (pinfunction "2_2") (pintype "passive"))
      (node (ref "R92") (pin "1") (pinfunction "1_1") (pintype "passive"))
      (node (ref "U4") (pin "14") (pinfunction "PH2(XCK2)_14") (pintype "bidirectional"))
    )
    (net (code "44") (name "EX2-FAN") (class "Default")
      (node (ref "Q4") (pin "4") (pinfunction "G_4") (pintype "passive"))
      (node (ref "R90") (pin "2") (pinfunction "2_2") (pintype "passive"))
      (node (ref "U4") (pin "25") (pinfunction "(OC1B/PCINT6)PB6_25") (pintype "bidirectional"))
    )
    (net (code "45") (name "EX2-HEAT") (class "Default")
      (node (ref "Q3") (pin "4") (pinfunction "G_4") (pintype "passive"))
      (node (ref "R83") (pin "2") (pinfunction "2_2") (pintype "passive"))
      (node (ref "U4") (pin "24") (pinfunction "(OC1A/PCINT5)PB5_24") (pintype "bidirectional"))
    )
    (net (code "46") (name "EX2-PWR-CHECK") (class "Default")
      (node (ref "R88") (pin "2") (pinfunction "2_2") (pintype "passive"))
      (node (ref "R94") (pin "1") (pinfunction "1_1") (pintype "passive"))
      (node (ref "U4") (pin "23") (pinfunction "(OC2A/PCINT4)PB4_23") (pintype "bidirectional"))
    )
    (net (code "47") (name "FAN1") (class "Default")
      (node (ref "Q6") (pin "4") (pinfunction "G_4") (pintype "passive"))
      (node (ref "R85") (pin "2") (pinfunction "2_2") (pintype "passive"))
      (node (ref "U4") (pin "40") (pinfunction "PL5(OC5C)_40") (pintype "bidirectional"))
    )
    (net (code "48") (name "FAN2") (class "Default")
      (node (ref "Q7") (pin "4") (pinfunction "G_4") (pintype "passive"))
      (node (ref "R30") (pin "2") (pinfunction "2_2") (pintype "passive"))
      (node (ref "U4") (pin "50") (pinfunction "(T0)PD7_50") (pintype "bidirectional"))
    )
    (net (code "49") (name "GND") (class "Default")
      (node (ref "12V") (pin "C") (pinfunction "C_C") (pintype "passive"))
      (node (ref "3.3V") (pin "C") (pinfunction "C_C") (pintype "passive"))
      (node (ref "5V") (pin "C") (pinfunction "C_C") (pintype "passive"))
      (node (ref "BOTSTEP-A") (pin "1") (pinfunction "GND1_1") (pintype "bidirectional"))
      (node (ref "BOTSTEP-A") (pin "7") (pinfunction "GND2_7") (pintype "bidirectional"))
      (node (ref "BOTSTEP-B") (pin "1") (pinfunction "GND1_1") (pintype "bidirectional"))
      (node (ref "BOTSTEP-B") (pin "7") (pinfunction "GND2_7") (pintype "bidirectional"))
      (node (ref "BOTSTEP-X") (pin "1") (pinfunction "GND1_1") (pintype "bidirectional"))
      (node (ref "BOTSTEP-X") (pin "7") (pinfunction "GND2_7") (pintype "bidirectional"))
      (node (ref "BOTSTEP-Y") (pin "1") (pinfunction "GND1_1") (pintype "bidirectional"))
      (node (ref "BOTSTEP-Y") (pin "7") (pinfunction "GND2_7") (pintype "bidirectional"))
      (node (ref "BOTSTEP-Z") (pin "1") (pinfunction "GND1_1") (pintype "bidirectional"))
      (node (ref "BOTSTEP-Z") (pin "7") (pinfunction "GND2_7") (pintype "bidirectional"))
      (node (ref "C10") (pin "2") (pinfunction "2_2") (pintype "passive"))
      (node (ref "C11") (pin "2") (pinfunction "2_2") (pintype "passive"))
      (node (ref "C12") (pin "2") (pinfunction "2_2") (pintype "passive"))
      (node (ref "C13") (pin "2") (pinfunction "2_2") (pintype "passive"))
      (node (ref "C14") (pin "2") (pinfunction "2_2") (pintype "passive"))
      (node (ref "C15") (pin "1") (pinfunction "1_1") (pintype "passive"))
      (node (ref "C16") (pin "2") (pinfunction "2_2") (pintype "passive"))
      (node (ref "C18") (pin "2") (pinfunction "2_2") (pintype "passive"))
      (node (ref "C19") (pin "2") (pinfunction "2_2") (pintype "passive"))
      (node (ref "C21") (pin "2") (pinfunction "2_2") (pintype "passive"))
      (node (ref "C22") (pin "2") (pinfunction "2_2") (pintype "passive"))
      (node (ref "C23") (pin "1") (pinfunction "1_1") (pintype "passive"))
      (node (ref "C24") (pin "1") (pinfunction "1_1") (pintype "passive"))
      (node (ref "C25") (pin "1") (pinfunction "1_1") (pintype "passive"))
      (node (ref "C26") (pin "1") (pinfunction "1_1") (pintype "passive"))
      (node (ref "C27") (pin "2") (pinfunction "2_2") (pintype "passive"))
      (node (ref "C28") (pin "1") (pinfunction "1_1") (pintype "passive"))
      (node (ref "C29") (pin "1") (pinfunction "1_1") (pintype "passive"))
      (node (ref "C3") (pin "1") (pinfunction "1_1") (pintype "passive"))
      (node (ref "C30") (pin "2") (pinfunction "2_2") (pintype "passive"))
      (node (ref "C31") (pin "-") (pinfunction "-_-") (pintype "passive"))
      (node (ref "C32") (pin "2") (pinfunction "2_2") (pintype "passive"))
      (node (ref "C33") (pin "2") (pinfunction "2_2") (pintype "passive"))
      (node (ref "C34") (pin "-") (pinfunction "-_-") (pintype "passive"))
      (node (ref "C35") (pin "-") (pinfunction "-_-") (pintype "passive"))
      (node (ref "C4") (pin "1") (pinfunction "1_1") (pintype "passive"))
      (node (ref "C5") (pin "1") (pinfunction "1_1") (pintype "passive"))
      (node (ref "C6") (pin "1") (pinfunction "1_1") (pintype "passive"))
      (node (ref "C7") (pin "1") (pinfunction "1_1") (pintype "passive"))
      (node (ref "C8") (pin "1") (pinfunction "1_1") (pintype "passive"))
      (node (ref "C9") (pin "1") (pinfunction "1_1") (pintype "passive"))
      (node (ref "CS-FAN") (pin "2") (pinfunction "1_2") (pintype "passive"))
      (node (ref "CUTOFF") (pin "2") (pinfunction "1_2") (pintype "passive"))
      (node (ref "HBP-THERM") (pin "2") (pinfunction "S_2") (pintype "passive"))
      (node (ref "HBP-THERM") (pin "3") (pinfunction "S_3") (pintype "passive"))
      (node (ref "I2C") (pin "2") (pinfunction "2_2") (pintype "passive"))
      (node (ref "ICSP1") (pin "6") (pinfunction "6_6") (pintype "passive"))
      (node (ref "ICSP2") (pin "6") (pinfunction "6_6") (pintype "passive"))
      (node (ref "INTERFACE") (pin "22") (pinfunction "22_22") (pintype "passive"))
      (node (ref "INTERFACE") (pin "24") (pinfunction "24_24") (pintype "passive"))
      (node (ref "INTERFACE") (pin "26") (pinfunction "26_26") (pintype "passive"))
      (node (ref "JP2") (pin "1") (pinfunction "1_1") (pintype "passive"))
      (node (ref "JP3") (pin "1") (pinfunction "1_1") (pintype "passive"))
      (node (ref "JP3") (pin "2") (pinfunction "2_2") (pintype "passive"))
      (node (ref "JP4") (pin "1") (pinfunction "1_1") (pintype "passive"))
      (node (ref "JP4") (pin "2") (pinfunction "2_2") (pintype "passive"))
      (node (ref "JP5") (pin "1") (pinfunction "1_1") (pintype "passive"))
      (node (ref "JP5") (pin "2") (pinfunction "2_2") (pintype "passive"))
      (node (ref "JP6") (pin "1") (pinfunction "1_1") (pintype "passive"))
      (node (ref "JP6") (pin "2") (pinfunction "2_2") (pintype "passive"))
      (node (ref "JP7") (pin "1") (pinfunction "1_1") (pintype "passive"))
      (node (ref "JP7") (pin "2") (pinfunction "2_2") (pintype "passive"))
      (node (ref "JP8") (pin "1") (pinfunction "1_1") (pintype "passive"))
      (node (ref "LS1") (pin "-") (pinfunction "+_-") (pintype "passive"))
      (node (ref "OVERHEAT") (pin "C") (pinfunction "C_C") (pintype "passive"))
      (node (ref "Q1") (pin "1") (pinfunction "S_1") (pintype "passive"))
      (node (ref "Q1") (pin "2") (pinfunction "S_2") (pintype "passive"))
      (node (ref "Q1") (pin "3") (pinfunction "S_3") (pintype "passive"))
      (node (ref "Q2") (pin "1") (pinfunction "S_1") (pintype "passive"))
      (node (ref "Q2") (pin "2") (pinfunction "S_2") (pintype "passive"))
      (node (ref "Q2") (pin "3") (pinfunction "S_3") (pintype "passive"))
      (node (ref "Q3") (pin "1") (pinfunction "S_1") (pintype "passive"))
      (node (ref "Q3") (pin "2") (pinfunction "S_2") (pintype "passive"))
      (node (ref "Q3") (pin "3") (pinfunction "S_3") (pintype "passive"))
      (node (ref "Q4") (pin "1") (pinfunction "S_1") (pintype "passive"))
      (node (ref "Q4") (pin "2") (pinfunction "S_2") (pintype "passive"))
      (node (ref "Q4") (pin "3") (pinfunction "S_3") (pintype "passive"))
      (node (ref "Q5") (pin "1") (pinfunction "S_1") (pintype "passive"))
      (node (ref "Q5") (pin "2") (pinfunction "S_2") (pintype "passive"))
      (node (ref "Q5") (pin "3") (pinfunction "S_3") (pintype "passive"))
      (node (ref "Q6") (pin "1") (pinfunction "S_1") (pintype "passive"))
      (node (ref "Q6") (pin "2") (pinfunction "S_2") (pintype "passive"))
      (node (ref "Q6") (pin "3") (pinfunction "S_3") (pintype "passive"))
      (node (ref "Q7") (pin "1") (pinfunction "S_1") (pintype "passive"))
      (node (ref "Q7") (pin "2") (pinfunction "S_2") (pintype "passive"))
      (node (ref "Q7") (pin "3") (pinfunction "S_3") (pintype "passive"))
      (node (ref "R1") (pin "1") (pinfunction "1_1") (pintype "passive"))
      (node (ref "R20") (pin "1") (pinfunction "1_1") (pintype "passive"))
      (node (ref "R21") (pin "1") (pinfunction "1_1") (pintype "passive"))
      (node (ref "R22") (pin "1") (pinfunction "1_1") (pintype "passive"))
      (node (ref "R23") (pin "1") (pinfunction "1_1") (pintype "passive"))
      (node (ref "R24") (pin "1") (pinfunction "1_1") (pintype "passive"))
      (node (ref "R25") (pin "1") (pinfunction "1_1") (pintype "passive"))
      (node (ref "R26") (pin "1") (pinfunction "1_1") (pintype "passive"))
      (node (ref "R27") (pin "1") (pinfunction "1_1") (pintype "passive"))
      (node (ref "R28") (pin "1") (pinfunction "1_1") (pintype "passive"))
      (node (ref "R29") (pin "1") (pinfunction "1_1") (pintype "passive"))
      (node (ref "R30") (pin "1") (pinfunction "1_1") (pintype "passive"))
      (node (ref "R67") (pin "2") (pinfunction "2_2") (pintype "passive"))
      (node (ref "R70") (pin "1") (pinfunction "1_1") (pintype "passive"))
      (node (ref "R74") (pin "1") (pinfunction "1_1") (pintype "passive"))
      (node (ref "R75") (pin "1") (pinfunction "1_1") (pintype "passive"))
      (node (ref "R76") (pin "1") (pinfunction "1_1") (pintype "passive"))
      (node (ref "R82") (pin "1") (pinfunction "1_1") (pintype "passive"))
      (node (ref "R83") (pin "1") (pinfunction "1_1") (pintype "passive"))
      (node (ref "R84") (pin "1") (pinfunction "1_1") (pintype "passive"))
      (node (ref "R85") (pin "1") (pinfunction "1_1") (pintype "passive"))
      (node (ref "R87") (pin "1") (pinfunction "1_1") (pintype "passive"))
      (node (ref "R88") (pin "1") (pinfunction "1_1") (pintype "passive"))
      (node (ref "R89") (pin "1") (pinfunction "1_1") (pintype "passive"))
      (node (ref "R90") (pin "1") (pinfunction "1_1") (pintype "passive"))
      (node (ref "R93") (pin "1") (pinfunction "1_1") (pintype "passive"))
      (node (ref "S1") (pin "3") (pinfunction "P_3") (pintype "passive"))
      (node (ref "TEMP1") (pin "2") (pinfunction "1_2") (pintype "passive"))
      (node (ref "TEMP2") (pin "2") (pinfunction "1_2") (pintype "passive"))
      (node (ref "U10") (pin "2") (pinfunction "VSS_2") (pintype "bidirectional"))
      (node (ref "U11") (pin "2") (pinfunction "VSS_2") (pintype "bidirectional"))
      (node (ref "U12") (pin "2") (pinfunction "VSS_2") (pintype "bidirectional"))
      (node (ref "U15") (pin "4") (pinfunction "VSS_4") (pintype "bidirectional"))
      (node (ref "U16") (pin "2") (pinfunction "S_2") (pintype "bidirectional"))
      (node (ref "U17") (pin "2") (pinfunction "S_2") (pintype "bidirectional"))
      (node (ref "U18") (pin "2") (pinfunction "S_2") (pintype "bidirectional"))
      (node (ref "U19") (pin "4") (pinfunction "GND_4") (pintype "bidirectional"))
      (node (ref "U3") (pin "3") (pinfunction "GND_3") (pintype "power_in"))
      (node (ref "U3") (pin "EXP") (pinfunction "PAD_EXP") (pintype "power_in"))
      (node (ref "U4") (pin "11") (pinfunction "GND_11") (pintype "power_in"))
      (node (ref "U4") (pin "32") (pinfunction "GND1_32") (pintype "power_in"))
      (node (ref "U4") (pin "62") (pinfunction "GND2_62") (pintype "power_in"))
      (node (ref "U4") (pin "81") (pinfunction "GND3_81") (pintype "power_in"))
      (node (ref "U4") (pin "99") (pinfunction "AGND_99") (pintype "power_in"))
      (node (ref "U5") (pin "4") (pinfunction "GND_4") (pintype "bidirectional"))
      (node (ref "U8") (pin "2") (pinfunction "VSS_2") (pintype "bidirectional"))
      (node (ref "U9") (pin "2") (pinfunction "VSS_2") (pintype "bidirectional"))
      (node (ref "UART") (pin "2") (pinfunction "2_2") (pintype "passive"))
      (node (ref "X-MAX") (pin "2") (pinfunction "S_2") (pintype "passive"))
      (node (ref "X-MAX") (pin "3") (pinfunction "S_3") (pintype "passive"))
      (node (ref "X-MIN") (pin "2") (pinfunction "S_2") (pintype "passive"))
      (node (ref "X-MIN") (pin "3") (pinfunction "S_3") (pintype "passive"))
      (node (ref "X3") (pin "10") (pinfunction "10_10") (pintype "passive"))
      (node (ref "X3") (pin "12") (pinfunction "12_12") (pintype "passive"))
      (node (ref "X3") (pin "13") (pinfunction "13_13") (pintype "passive"))
      (node (ref "X3") (pin "14") (pinfunction "14_14") (pintype "passive"))
      (node (ref "X3") (pin "5") (pinfunction "5_5") (pintype "passive"))
      (node (ref "X3") (pin "6") (pinfunction "6_6") (pintype "passive"))
      (node (ref "X3") (pin "8") (pinfunction "8_8") (pintype "passive"))
      (node (ref "X3") (pin "9") (pinfunction "9_9") (pintype "passive"))
      (node (ref "Y-MAX") (pin "2") (pinfunction "S_2") (pintype "passive"))
      (node (ref "Y-MAX") (pin "3") (pinfunction "S_3") (pintype "passive"))
      (node (ref "Y-MIN") (pin "2") (pinfunction "S_2") (pintype "passive"))
      (node (ref "Y-MIN") (pin "3") (pinfunction "S_3") (pintype "passive"))
      (node (ref "Z-MAX") (pin "2") (pinfunction "S_2") (pintype "passive"))
      (node (ref "Z-MAX") (pin "3") (pinfunction "S_3") (pintype "passive"))
      (node (ref "Z-MIN") (pin "2") (pinfunction "S_2") (pintype "passive"))
      (node (ref "Z-MIN") (pin "3") (pinfunction "S_3") (pintype "passive"))
    )
    (net (code "50") (name "HBP") (class "Default")
      (node (ref "Q5") (pin "4") (pinfunction "G_4") (pintype "passive"))
      (node (ref "R84") (pin "2") (pinfunction "2_2") (pintype "passive"))
      (node (ref "U4") (pin "39") (pinfunction "PL4(OC5B)_39") (pintype "bidirectional"))
    )
    (net (code "51") (name "HBP-THERM") (class "Default")
      (node (ref "HBP-THERM") (pin "4") (pinfunction "S_4") (pintype "passive"))
      (node (ref "R65") (pin "2") (pinfunction "2_2") (pintype "passive"))
      (node (ref "TP27") (pin "TP") (pinfunction "TP_TP") (pintype "input"))
      (node (ref "U4") (pin "82") (pinfunction "PK7(ADC15/PCINT23)_82") (pintype "bidirectional"))
    )
    (net (code "52") (name "I4-UP") (class "Default")
      (node (ref "INTERFACE") (pin "4") (pinfunction "4_4") (pintype "passive"))
      (node (ref "U4") (pin "67") (pinfunction "PJ4(PCINT13)_67") (pintype "bidirectional"))
    )
    (net (code "53") (name "I5-DOWN") (class "Default")
      (node (ref "INTERFACE") (pin "5") (pinfunction "5_5") (pintype "passive"))
      (node (ref "U4") (pin "66") (pinfunction "PJ3(PCINT12)_66") (pintype "bidirectional"))
    )
    (net (code "54") (name "I6-LEFT") (class "Default")
      (node (ref "INTERFACE") (pin "6") (pinfunction "6_6") (pintype "passive"))
      (node (ref "U4") (pin "65") (pinfunction "PJ2(XCK3/PCINT11)_65") (pintype "bidirectional"))
    )
    (net (code "55") (name "I7-RIGHT") (class "Default")
      (node (ref "INTERFACE") (pin "7") (pinfunction "7_7") (pintype "passive"))
      (node (ref "U4") (pin "64") (pinfunction "PJ1(TXD3/PCINT10)_64") (pintype "bidirectional"))
    )
    (net (code "56") (name "I8-CENTER") (class "Default")
      (node (ref "INTERFACE") (pin "8") (pinfunction "8_8") (pintype "passive"))
      (node (ref "U4") (pin "63") (pinfunction "PJ0(RXD3/PCINT9)_63") (pintype "bidirectional"))
    )
    (net (code "57") (name "I9-DETECT") (class "Default")
      (node (ref "INTERFACE") (pin "9") (pinfunction "9_9") (pintype "passive"))
      (node (ref "R70") (pin "2") (pinfunction "2_2") (pintype "passive"))
      (node (ref "U4") (pin "60") (pinfunction "(A15)PC7_60") (pintype "bidirectional"))
    )
    (net (code "58") (name "I10-GLED") (class "Default")
      (node (ref "INTERFACE") (pin "10") (pinfunction "10_10") (pintype "passive"))
      (node (ref "U4") (pin "59") (pinfunction "(A14)PC6_59") (pintype "bidirectional"))
    )
    (net (code "59") (name "I11-RLED") (class "Default")
      (node (ref "INTERFACE") (pin "11") (pinfunction "11_11") (pintype "passive"))
      (node (ref "U4") (pin "58") (pinfunction "(A13)PC5_58") (pintype "bidirectional"))
    )
    (net (code "60") (name "I12-LCD-STROBE") (class "Default")
      (node (ref "INTERFACE") (pin "12") (pinfunction "12_12") (pintype "passive"))
      (node (ref "U4") (pin "57") (pinfunction "(A12)PC4_57") (pintype "bidirectional"))
    )
    (net (code "61") (name "I13-LCD-DATA") (class "Default")
      (node (ref "INTERFACE") (pin "13") (pinfunction "13_13") (pintype "passive"))
      (node (ref "U4") (pin "56") (pinfunction "(A11)PC3_56") (pintype "bidirectional"))
    )
    (net (code "62") (name "I14-LCD-CLK") (class "Default")
      (node (ref "INTERFACE") (pin "14") (pinfunction "14_14") (pintype "passive"))
      (node (ref "U4") (pin "55") (pinfunction "(A10)PC2_55") (pintype "bidirectional"))
    )
    (net (code "63") (name "Net-(+CFAN1-B-1)") (class "Default")
      (node (ref "+CFAN1-") (pin "2") (pinfunction "1_2") (pintype "passive"))
      (node (ref "FET7") (pin "C") (pinfunction "C_C") (pintype "passive"))
      (node (ref "Q7") (pin "MB") (pinfunction "D_MB") (pintype "passive"))
    )
    (net (code "64") (name "Net-(3.3V-PadA)") (class "Default")
      (node (ref "3.3V") (pin "A") (pinfunction "A_A") (pintype "passive"))
      (node (ref "R81") (pin "2") (pinfunction "2_2") (pintype "passive"))
    )
    (net (code "65") (name "Net-(5V-PadA)") (class "Default")
      (node (ref "5V") (pin "A") (pinfunction "A_A") (pintype "passive"))
      (node (ref "R79") (pin "2") (pinfunction "2_2") (pintype "passive"))
    )
    (net (code "66") (name "Net-(12V-PadA)") (class "Default")
      (node (ref "12V") (pin "A") (pinfunction "A_A") (pintype "passive"))
      (node (ref "R80") (pin "1") (pinfunction "1_1") (pintype "passive"))
    )
    (net (code "67") (name "Net-(A-STEPPERA-S)") (class "Default")
      (node (ref "A-STEPPER") (pin "1") (pinfunction "S_1") (pintype "passive"))
      (node (ref "BOTSTEP-A") (pin "4") (pinfunction "OUT1A_4") (pintype "output"))
    )
    (net (code "68") (name "Net-(A-STEPPERB-S)") (class "Default")
      (node (ref "A-STEPPER") (pin "2") (pinfunction "S_2") (pintype "passive"))
      (node (ref "BOTSTEP-A") (pin "3") (pinfunction "OUT1B_3") (pintype "output"))
    )
    (net (code "69") (name "Net-(A-STEPPERC-S)") (class "Default")
      (node (ref "A-STEPPER") (pin "3") (pinfunction "S_3") (pintype "passive"))
      (node (ref "BOTSTEP-A") (pin "5") (pinfunction "OUT2A_5") (pintype "output"))
    )
    (net (code "70") (name "Net-(A-STEPPERD-S)") (class "Default")
      (node (ref "A-STEPPER") (pin "4") (pinfunction "S_4") (pintype "passive"))
      (node (ref "BOTSTEP-A") (pin "6") (pinfunction "OUT2B_6") (pintype "output"))
    )
    (net (code "71") (name "Net-(B-STEPPERA-S)") (class "Default")
      (node (ref "B-STEPPER") (pin "1") (pinfunction "S_1") (pintype "passive"))
      (node (ref "BOTSTEP-B") (pin "4") (pinfunction "OUT1A_4") (pintype "output"))
    )
    (net (code "72") (name "Net-(B-STEPPERB-S)") (class "Default")
      (node (ref "B-STEPPER") (pin "2") (pinfunction "S_2") (pintype "passive"))
      (node (ref "BOTSTEP-B") (pin "3") (pinfunction "OUT1B_3") (pintype "output"))
    )
    (net (code "73") (name "Net-(B-STEPPERC-S)") (class "Default")
      (node (ref "B-STEPPER") (pin "3") (pinfunction "S_3") (pintype "passive"))
      (node (ref "BOTSTEP-B") (pin "5") (pinfunction "OUT2A_5") (pintype "output"))
    )
    (net (code "74") (name "Net-(B-STEPPERD-S)") (class "Default")
      (node (ref "B-STEPPER") (pin "4") (pinfunction "S_4") (pintype "passive"))
      (node (ref "BOTSTEP-B") (pin "6") (pinfunction "OUT2B_6") (pintype "output"))
    )
    (net (code "75") (name "Net-(BOTSTEP-A-MS1)") (class "Default")
      (node (ref "BOTSTEP-A") (pin "10") (pinfunction "MS1_10") (pintype "input"))
      (node (ref "R14") (pin "1") (pinfunction "1_1") (pintype "passive"))
      (node (ref "R26") (pin "2") (pinfunction "2_2") (pintype "passive"))
    )
    (net (code "76") (name "Net-(BOTSTEP-A-MS2)") (class "Default")
      (node (ref "BOTSTEP-A") (pin "11") (pinfunction "MS2_11") (pintype "input"))
      (node (ref "R15") (pin "1") (pinfunction "1_1") (pintype "passive"))
      (node (ref "R27") (pin "2") (pinfunction "2_2") (pintype "passive"))
    )
    (net (code "77") (name "Net-(BOTSTEP-A-RST)") (class "Default")
      (node (ref "BOTSTEP-A") (pin "13") (pinfunction "RST_13") (pintype "input"))
      (node (ref "BOTSTEP-A") (pin "14") (pinfunction "SLP_14") (pintype "input"))
      (node (ref "R16") (pin "1") (pinfunction "1_1") (pintype "passive"))
    )
    (net (code "78") (name "Net-(BOTSTEP-A-VREF)") (class "Default")
      (node (ref "BOTSTEP-A") (pin "12") (pinfunction "VREF_12") (pintype "input"))
      (node (ref "U11") (pin "5") (pinfunction "W_5") (pintype "bidirectional"))
    )
    (net (code "79") (name "Net-(BOTSTEP-B-MS1)") (class "Default")
      (node (ref "BOTSTEP-B") (pin "10") (pinfunction "MS1_10") (pintype "input"))
      (node (ref "R17") (pin "1") (pinfunction "1_1") (pintype "passive"))
      (node (ref "R28") (pin "2") (pinfunction "2_2") (pintype "passive"))
    )
    (net (code "80") (name "Net-(BOTSTEP-B-MS2)") (class "Default")
      (node (ref "BOTSTEP-B") (pin "11") (pinfunction "MS2_11") (pintype "input"))
      (node (ref "R18") (pin "1") (pinfunction "1_1") (pintype "passive"))
      (node (ref "R29") (pin "2") (pinfunction "2_2") (pintype "passive"))
    )
    (net (code "81") (name "Net-(BOTSTEP-B-RST)") (class "Default")
      (node (ref "BOTSTEP-B") (pin "13") (pinfunction "RST_13") (pintype "input"))
      (node (ref "BOTSTEP-B") (pin "14") (pinfunction "SLP_14") (pintype "input"))
      (node (ref "R19") (pin "1") (pinfunction "1_1") (pintype "passive"))
    )
    (net (code "82") (name "Net-(BOTSTEP-B-VREF)") (class "Default")
      (node (ref "BOTSTEP-B") (pin "12") (pinfunction "VREF_12") (pintype "input"))
      (node (ref "U12") (pin "5") (pinfunction "W_5") (pintype "bidirectional"))
    )
    (net (code "83") (name "Net-(BOTSTEP-X-MS1)") (class "Default")
      (node (ref "BOTSTEP-X") (pin "10") (pinfunction "MS1_10") (pintype "input"))
      (node (ref "R20") (pin "2") (pinfunction "2_2") (pintype "passive"))
      (node (ref "R5") (pin "1") (pinfunction "1_1") (pintype "passive"))
    )
    (net (code "84") (name "Net-(BOTSTEP-X-MS2)") (class "Default")
      (node (ref "BOTSTEP-X") (pin "11") (pinfunction "MS2_11") (pintype "input"))
      (node (ref "R21") (pin "2") (pinfunction "2_2") (pintype "passive"))
      (node (ref "R6") (pin "1") (pinfunction "1_1") (pintype "passive"))
    )
    (net (code "85") (name "Net-(BOTSTEP-X-OUT1A)") (class "Default")
      (node (ref "BOTSTEP-X") (pin "4") (pinfunction "OUT1A_4") (pintype "output"))
      (node (ref "X-STEPPER") (pin "1") (pinfunction "S_1") (pintype "passive"))
    )
    (net (code "86") (name "Net-(BOTSTEP-X-OUT1B)") (class "Default")
      (node (ref "BOTSTEP-X") (pin "3") (pinfunction "OUT1B_3") (pintype "output"))
      (node (ref "X-STEPPER") (pin "2") (pinfunction "S_2") (pintype "passive"))
    )
    (net (code "87") (name "Net-(BOTSTEP-X-OUT2A)") (class "Default")
      (node (ref "BOTSTEP-X") (pin "5") (pinfunction "OUT2A_5") (pintype "output"))
      (node (ref "X-STEPPER") (pin "3") (pinfunction "S_3") (pintype "passive"))
    )
    (net (code "88") (name "Net-(BOTSTEP-X-OUT2B)") (class "Default")
      (node (ref "BOTSTEP-X") (pin "6") (pinfunction "OUT2B_6") (pintype "output"))
      (node (ref "X-STEPPER") (pin "4") (pinfunction "S_4") (pintype "passive"))
    )
    (net (code "89") (name "Net-(BOTSTEP-X-RST)") (class "Default")
      (node (ref "BOTSTEP-X") (pin "13") (pinfunction "RST_13") (pintype "input"))
      (node (ref "BOTSTEP-X") (pin "14") (pinfunction "SLP_14") (pintype "input"))
      (node (ref "R7") (pin "1") (pinfunction "1_1") (pintype "passive"))
    )
    (net (code "90") (name "Net-(BOTSTEP-X-VREF)") (class "Default")
      (node (ref "BOTSTEP-X") (pin "12") (pinfunction "VREF_12") (pintype "input"))
      (node (ref "U8") (pin "5") (pinfunction "W_5") (pintype "bidirectional"))
    )
    (net (code "91") (name "Net-(BOTSTEP-Y-MS1)") (class "Default")
      (node (ref "BOTSTEP-Y") (pin "10") (pinfunction "MS1_10") (pintype "input"))
      (node (ref "R22") (pin "2") (pinfunction "2_2") (pintype "passive"))
      (node (ref "R8") (pin "1") (pinfunction "1_1") (pintype "passive"))
    )
    (net (code "92") (name "Net-(BOTSTEP-Y-MS2)") (class "Default")
      (node (ref "BOTSTEP-Y") (pin "11") (pinfunction "MS2_11") (pintype "input"))
      (node (ref "R23") (pin "2") (pinfunction "2_2") (pintype "passive"))
      (node (ref "R9") (pin "1") (pinfunction "1_1") (pintype "passive"))
    )
    (net (code "93") (name "Net-(BOTSTEP-Y-OUT1A)") (class "Default")
      (node (ref "BOTSTEP-Y") (pin "4") (pinfunction "OUT1A_4") (pintype "output"))
      (node (ref "Y-STEPPER") (pin "1") (pinfunction "S_1") (pintype "passive"))
    )
    (net (code "94") (name "Net-(BOTSTEP-Y-OUT1B)") (class "Default")
      (node (ref "BOTSTEP-Y") (pin "3") (pinfunction "OUT1B_3") (pintype "output"))
      (node (ref "Y-STEPPER") (pin "2") (pinfunction "S_2") (pintype "passive"))
    )
    (net (code "95") (name "Net-(BOTSTEP-Y-OUT2A)") (class "Default")
      (node (ref "BOTSTEP-Y") (pin "5") (pinfunction "OUT2A_5") (pintype "output"))
      (node (ref "Y-STEPPER") (pin "3") (pinfunction "S_3") (pintype "passive"))
    )
    (net (code "96") (name "Net-(BOTSTEP-Y-OUT2B)") (class "Default")
      (node (ref "BOTSTEP-Y") (pin "6") (pinfunction "OUT2B_6") (pintype "output"))
      (node (ref "Y-STEPPER") (pin "4") (pinfunction "S_4") (pintype "passive"))
    )
    (net (code "97") (name "Net-(BOTSTEP-Y-RST)") (class "Default")
      (node (ref "BOTSTEP-Y") (pin "13") (pinfunction "RST_13") (pintype "input"))
      (node (ref "BOTSTEP-Y") (pin "14") (pinfunction "SLP_14") (pintype "input"))
      (node (ref "R10") (pin "1") (pinfunction "1_1") (pintype "passive"))
    )
    (net (code "98") (name "Net-(BOTSTEP-Y-VREF)") (class "Default")
      (node (ref "BOTSTEP-Y") (pin "12") (pinfunction "VREF_12") (pintype "input"))
      (node (ref "U9") (pin "5") (pinfunction "W_5") (pintype "bidirectional"))
    )
    (net (code "99") (name "Net-(BOTSTEP-Z-MS1)") (class "Default")
      (node (ref "BOTSTEP-Z") (pin "10") (pinfunction "MS1_10") (pintype "input"))
      (node (ref "R11") (pin "1") (pinfunction "1_1") (pintype "passive"))
      (node (ref "R24") (pin "2") (pinfunction "2_2") (pintype "passive"))
    )
    (net (code "100") (name "Net-(BOTSTEP-Z-MS2)") (class "Default")
      (node (ref "BOTSTEP-Z") (pin "11") (pinfunction "MS2_11") (pintype "input"))
      (node (ref "R12") (pin "1") (pinfunction "1_1") (pintype "passive"))
      (node (ref "R25") (pin "2") (pinfunction "2_2") (pintype "passive"))
    )
    (net (code "101") (name "Net-(BOTSTEP-Z-OUT1A)") (class "Default")
      (node (ref "BOTSTEP-Z") (pin "4") (pinfunction "OUT1A_4") (pintype "output"))
      (node (ref "Z-STEPPER") (pin "1") (pinfunction "S_1") (pintype "passive"))
    )
    (net (code "102") (name "Net-(BOTSTEP-Z-OUT1B)") (class "Default")
      (node (ref "BOTSTEP-Z") (pin "3") (pinfunction "OUT1B_3") (pintype "output"))
      (node (ref "Z-STEPPER") (pin "2") (pinfunction "S_2") (pintype "passive"))
    )
    (net (code "103") (name "Net-(BOTSTEP-Z-OUT2A)") (class "Default")
      (node (ref "BOTSTEP-Z") (pin "5") (pinfunction "OUT2A_5") (pintype "output"))
      (node (ref "Z-STEPPER") (pin "3") (pinfunction "S_3") (pintype "passive"))
    )
    (net (code "104") (name "Net-(BOTSTEP-Z-OUT2B)") (class "Default")
      (node (ref "BOTSTEP-Z") (pin "6") (pinfunction "OUT2B_6") (pintype "output"))
      (node (ref "Z-STEPPER") (pin "4") (pinfunction "S_4") (pintype "passive"))
    )
    (net (code "105") (name "Net-(BOTSTEP-Z-RST)") (class "Default")
      (node (ref "BOTSTEP-Z") (pin "13") (pinfunction "RST_13") (pintype "input"))
      (node (ref "BOTSTEP-Z") (pin "14") (pinfunction "SLP_14") (pintype "input"))
      (node (ref "R13") (pin "1") (pinfunction "1_1") (pintype "passive"))
    )
    (net (code "106") (name "Net-(BOTSTEP-Z-VREF)") (class "Default")
      (node (ref "BOTSTEP-Z") (pin "12") (pinfunction "VREF_12") (pintype "input"))
      (node (ref "U10") (pin "5") (pinfunction "W_5") (pintype "bidirectional"))
    )
    (net (code "107") (name "Net-(CFAN2B-1)") (class "Default")
      (node (ref "CFAN2") (pin "2") (pinfunction "1_2") (pintype "passive"))
      (node (ref "FET6") (pin "C") (pinfunction "C_C") (pintype "passive"))
      (node (ref "Q6") (pin "MB") (pinfunction "D_MB") (pintype "passive"))
    )
    (net (code "108") (name "Net-(CUTOFF-Pad1)") (class "Default")
      (node (ref "CUTOFF") (pin "1") (pinfunction "1_1") (pintype "passive"))
      (node (ref "R96") (pin "2") (pinfunction "2_2") (pintype "passive"))
    )
    (net (code "109") (name "Net-(DEBUG1-PadC)") (class "Default")
      (node (ref "DEBUG1") (pin "C") (pinfunction "C_C") (pintype "passive"))
      (node (ref "R1") (pin "2") (pinfunction "2_2") (pintype "passive"))
    )
    (net (code "110") (name "Net-(DEBUG2-PadC)") (class "Default")
      (node (ref "DEBUG2") (pin "C") (pinfunction "C_C") (pintype "passive"))
      (node (ref "R74") (pin "2") (pinfunction "2_2") (pintype "passive"))
    )
    (net (code "111") (name "Net-(DEBUG3-PadC)") (class "Default")
      (node (ref "DEBUG3") (pin "C") (pinfunction "C_C") (pintype "passive"))
      (node (ref "R75") (pin "2") (pinfunction "2_2") (pintype "passive"))
    )
    (net (code "112") (name "Net-(DEBUG4-PadC)") (class "Default")
      (node (ref "DEBUG4") (pin "C") (pinfunction "C_C") (pintype "passive"))
      (node (ref "R76") (pin "2") (pinfunction "2_2") (pintype "passive"))
    )
    (net (code "113") (name "Net-(EX1B-1)") (class "Default")
      (node (ref "EX1") (pin "2") (pinfunction "1_2") (pintype "passive"))
      (node (ref "FET1") (pin "C") (pinfunction "C_C") (pintype "passive"))
      (node (ref "Q1") (pin "MB") (pinfunction "D_MB") (pintype "passive"))
    )
    (net (code "114") (name "Net-(EX1D-1)") (class "Default")
      (node (ref "EX1") (pin "4") (pinfunction "1_4") (pintype "passive"))
      (node (ref "FET2") (pin "C") (pinfunction "C_C") (pintype "passive"))
      (node (ref "Q2") (pin "MB") (pinfunction "D_MB") (pintype "passive"))
    )
    (net (code "115") (name "Net-(EX2B-1)") (class "Default")
      (node (ref "EX2") (pin "2") (pinfunction "1_2") (pintype "passive"))
      (node (ref "FET3") (pin "C") (pinfunction "C_C") (pintype "passive"))
      (node (ref "Q3") (pin "MB") (pinfunction "D_MB") (pintype "passive"))
    )
    (net (code "116") (name "Net-(EX2D-1)") (class "Default")
      (node (ref "EX2") (pin "4") (pinfunction "1_4") (pintype "passive"))
      (node (ref "FET4") (pin "C") (pinfunction "C_C") (pintype "passive"))
      (node (ref "Q4") (pin "MB") (pinfunction "D_MB") (pintype "passive"))
    )
    (net (code "117") (name "Net-(FET1-PadA)") (class "Default")
      (node (ref "FET1") (pin "A") (pinfunction "A_A") (pintype "passive"))
      (node (ref "R97") (pin "1") (pinfunction "1_1") (pintype "passive"))
    )
    (net (code "118") (name "Net-(FET2-PadA)") (class "Default")
      (node (ref "FET2") (pin "A") (pinfunction "A_A") (pintype "passive"))
      (node (ref "R98") (pin "1") (pinfunction "1_1") (pintype "passive"))
    )
    (net (code "119") (name "Net-(FET3-PadA)") (class "Default")
      (node (ref "FET3") (pin "A") (pinfunction "A_A") (pintype "passive"))
      (node (ref "R99") (pin "1") (pinfunction "1_1") (pintype "passive"))
    )
    (net (code "120") (name "Net-(FET4-PadA)") (class "Default")
      (node (ref "FET4") (pin "A") (pinfunction "A_A") (pintype "passive"))
      (node (ref "R100") (pin "1") (pinfunction "1_1") (pintype "passive"))
    )
    (net (code "121") (name "Net-(FET5-PadA)") (class "Default")
      (node (ref "FET5") (pin "A") (pinfunction "A_A") (pintype "passive"))
      (node (ref "R101") (pin "1") (pinfunction "1_1") (pintype "passive"))
    )
    (net (code "122") (name "Net-(FET6-PadA)") (class "Default")
      (node (ref "FET6") (pin "A") (pinfunction "A_A") (pintype "passive"))
      (node (ref "R102") (pin "1") (pinfunction "1_1") (pintype "passive"))
    )
    (net (code "123") (name "Net-(FET7-PadA)") (class "Default")
      (node (ref "FET7") (pin "A") (pinfunction "A_A") (pintype "passive"))
      (node (ref "R4") (pin "1") (pinfunction "1_1") (pintype "passive"))
    )
    (net (code "124") (name "Net-(HBPB-1)") (class "Default")
      (node (ref "FET5") (pin "C") (pinfunction "C_C") (pintype "passive"))
      (node (ref "HBP") (pin "2") (pinfunction "1_2") (pintype "passive"))
      (node (ref "Q5") (pin "MB") (pinfunction "D_MB") (pintype "passive"))
    )
    (net (code "125") (name "Net-(L1-Pad2)") (class "Default")
      (node (ref "L1") (pin "2") (pinfunction "2_2") (pintype "passive"))
      (node (ref "VR1") (pin "1") (pinfunction "1_1") (pintype "passive"))
      (node (ref "VR2") (pin "1") (pinfunction "1_1") (pintype "passive"))
      (node (ref "X2") (pin "P$1") (pinfunction "P$1_P$1") (pintype "bidirectional"))
      (node (ref "X2") (pin "P$2") (pinfunction "P$2_P$2") (pintype "bidirectional"))
    )
    (net (code "126") (name "Net-(OVERHEAT-PadA)") (class "Default")
      (node (ref "OVERHEAT") (pin "A") (pinfunction "A_A") (pintype "passive"))
      (node (ref "R91") (pin "2") (pinfunction "2_2") (pintype "passive"))
    )
    (net (code "127") (name "Net-(R72-Pad2)") (class "Default")
      (node (ref "R72") (pin "2") (pinfunction "2_2") (pintype "passive"))
      (node (ref "TX") (pin "A") (pinfunction "A_A") (pintype "passive"))
    )
    (net (code "128") (name "Net-(R73-Pad2)") (class "Default")
      (node (ref "R73") (pin "2") (pinfunction "2_2") (pintype "passive"))
      (node (ref "RX") (pin "A") (pinfunction "A_A") (pintype "passive"))
    )
    (net (code "129") (name "Net-(RGB-LEDB-S)") (class "Default")
      (node (ref "RGB-LED") (pin "2") (pinfunction "S_2") (pintype "passive"))
      (node (ref "U16") (pin "3") (pinfunction "D_3") (pintype "bidirectional"))
    )
    (net (code "130") (name "Net-(RGB-LEDC-S)") (class "Default")
      (node (ref "RGB-LED") (pin "3") (pinfunction "S_3") (pintype "passive"))
      (node (ref "U17") (pin "3") (pinfunction "D_3") (pintype "bidirectional"))
    )
    (net (code "131") (name "Net-(RGB-LEDD-S)") (class "Default")
      (node (ref "RGB-LED") (pin "4") (pinfunction "S_4") (pintype "passive"))
      (node (ref "U18") (pin "3") (pinfunction "D_3") (pintype "bidirectional"))
    )
    (net (code "132") (name "Net-(U3-(CTS{slash}HWB{slash}AIN6{slash}TO{slash}INT7)PD7)") (class "Default")
      (node (ref "C20") (pin "2") (pinfunction "2_2") (pintype "passive"))
      (node (ref "U3") (pin "13") (pinfunction "(CTS/HWB/AIN6/TO/INT7)PD7_13") (pintype "bidirectional"))
    )
    (net (code "133") (name "Net-(U3-(RXD1{slash}AIN1{slash}INT2)PD2)") (class "Default")
      (node (ref "R71") (pin "1") (pinfunction "1_1") (pintype "passive"))
      (node (ref "U3") (pin "8") (pinfunction "(RXD1/AIN1/INT2)PD2_8") (pintype "bidirectional"))
    )
    (net (code "134") (name "Net-(U3-(TXD1{slash}INT3)PD3)") (class "Default")
      (node (ref "R68") (pin "1") (pinfunction "1_1") (pintype "passive"))
      (node (ref "U3") (pin "9") (pinfunction "(TXD1/INT3)PD3_9") (pintype "bidirectional"))
    )
    (net (code "135") (name "Net-(U3-D+)") (class "Default")
      (node (ref "R66") (pin "1") (pinfunction "1_1") (pintype "passive"))
      (node (ref "U3") (pin "29") (pinfunction "D+_29") (pintype "bidirectional"))
    )
    (net (code "136") (name "Net-(U3-D-)") (class "Default")
      (node (ref "R69") (pin "1") (pinfunction "1_1") (pintype "passive"))
      (node (ref "U3") (pin "30") (pinfunction "D-_30") (pintype "bidirectional"))
    )
    (net (code "137") (name "Net-(U3-UCAP)") (class "Default")
      (node (ref "C17") (pin "2") (pinfunction "2_2") (pintype "passive"))
      (node (ref "U3") (pin "27") (pinfunction "UCAP_27") (pintype "passive"))
    )
    (net (code "138") (name "Net-(U3-XTAL1)") (class "Default")
      (node (ref "C25") (pin "2") (pinfunction "2_2") (pintype "passive"))
      (node (ref "U3") (pin "1") (pinfunction "XTAL1_1") (pintype "bidirectional"))
      (node (ref "Y1") (pin "1") (pinfunction "1_1") (pintype "passive"))
    )
    (net (code "139") (name "Net-(U3-XTAL2(PC0))") (class "Default")
      (node (ref "C26") (pin "2") (pinfunction "2_2") (pintype "passive"))
      (node (ref "U3") (pin "2") (pinfunction "XTAL2(PC0)_2") (pintype "bidirectional"))
      (node (ref "Y1") (pin "2") (pinfunction "2_2") (pintype "passive"))
    )
    (net (code "140") (name "Net-(U4-XTAL1)") (class "Default")
      (node (ref "C28") (pin "2") (pinfunction "2_2") (pintype "passive"))
      (node (ref "U4") (pin "34") (pinfunction "XTAL1_34") (pintype "input"))
      (node (ref "Y2") (pin "1") (pinfunction "1_1") (pintype "passive"))
    )
    (net (code "141") (name "Net-(U4-XTAL2)") (class "Default")
      (node (ref "C29") (pin "2") (pinfunction "2_2") (pintype "passive"))
      (node (ref "U4") (pin "33") (pinfunction "XTAL2_33") (pintype "output"))
      (node (ref "Y2") (pin "2") (pinfunction "2_2") (pintype "passive"))
    )
    (net (code "142") (name "Net-(U5-B1)") (class "Default")
      (node (ref "U5") (pin "2") (pinfunction "B1_2") (pintype "bidirectional"))
      (node (ref "U5") (pin "3") (pinfunction "Y2_3") (pintype "bidirectional"))
    )
    (net (code "143") (name "Net-(U6-A)") (class "Default")
      (node (ref "R108") (pin "1") (pinfunction "1_1") (pintype "passive"))
      (node (ref "U6") (pin "1") (pinfunction "A_1") (pintype "bidirectional"))
    )
    (net (code "144") (name "Net-(U7-A)") (class "Default")
      (node (ref "R109") (pin "1") (pinfunction "1_1") (pintype "passive"))
      (node (ref "U7") (pin "1") (pinfunction "A_1") (pintype "bidirectional"))
    )
    (net (code "145") (name "Net-(U8-A)") (class "Default")
      (node (ref "R34") (pin "1") (pinfunction "1_1") (pintype "passive"))
      (node (ref "U8") (pin "6") (pinfunction "A_6") (pintype "bidirectional"))
    )
    (net (code "146") (name "Net-(U8-SDA)") (class "Default")
      (node (ref "R103") (pin "1") (pinfunction "1_1") (pintype "passive"))
      (node (ref "U8") (pin "4") (pinfunction "SDA_4") (pintype "bidirectional"))
      (node (ref "X-POT") (pin "TP") (pinfunction "TP_TP") (pintype "input"))
    )
    (net (code "147") (name "Net-(U9-A)") (class "Default")
      (node (ref "R35") (pin "1") (pinfunction "1_1") (pintype "passive"))
      (node (ref "U9") (pin "6") (pinfunction "A_6") (pintype "bidirectional"))
    )
    (net (code "148") (name "Net-(U9-SDA)") (class "Default")
      (node (ref "R104") (pin "1") (pinfunction "1_1") (pintype "passive"))
      (node (ref "U9") (pin "4") (pinfunction "SDA_4") (pintype "bidirectional"))
      (node (ref "Y-POT") (pin "TP") (pinfunction "TP_TP") (pintype "input"))
    )
    (net (code "149") (name "Net-(U10-A)") (class "Default")
      (node (ref "R36") (pin "1") (pinfunction "1_1") (pintype "passive"))
      (node (ref "U10") (pin "6") (pinfunction "A_6") (pintype "bidirectional"))
    )
    (net (code "150") (name "Net-(U10-SDA)") (class "Default")
      (node (ref "R105") (pin "1") (pinfunction "1_1") (pintype "passive"))
      (node (ref "U10") (pin "4") (pinfunction "SDA_4") (pintype "bidirectional"))
      (node (ref "Z-POT") (pin "TP") (pinfunction "TP_TP") (pintype "input"))
    )
    (net (code "151") (name "Net-(U11-A)") (class "Default")
      (node (ref "R37") (pin "1") (pinfunction "1_1") (pintype "passive"))
      (node (ref "U11") (pin "6") (pinfunction "A_6") (pintype "bidirectional"))
    )
    (net (code "152") (name "Net-(U11-SDA)") (class "Default")
      (node (ref "A-POT") (pin "TP") (pinfunction "TP_TP") (pintype "input"))
      (node (ref "R106") (pin "1") (pinfunction "1_1") (pintype "passive"))
      (node (ref "U11") (pin "4") (pinfunction "SDA_4") (pintype "bidirectional"))
    )
    (net (code "153") (name "Net-(U12-A)") (class "Default")
      (node (ref "R38") (pin "1") (pinfunction "1_1") (pintype "passive"))
      (node (ref "U12") (pin "6") (pinfunction "A_6") (pintype "bidirectional"))
    )
    (net (code "154") (name "Net-(U12-SDA)") (class "Default")
      (node (ref "B-POT") (pin "TP") (pinfunction "TP_TP") (pintype "input"))
      (node (ref "R107") (pin "1") (pinfunction "1_1") (pintype "passive"))
      (node (ref "U12") (pin "4") (pinfunction "SDA_4") (pintype "bidirectional"))
    )
    (net (code "155") (name "Net-(U15-LED0)") (class "Default")
      (node (ref "R110") (pin "2") (pinfunction "2_2") (pintype "passive"))
      (node (ref "U15") (pin "1") (pinfunction "LED0_1") (pintype "bidirectional"))
    )
    (net (code "156") (name "Net-(U15-LED1)") (class "Default")
      (node (ref "R111") (pin "2") (pinfunction "2_2") (pintype "passive"))
      (node (ref "U15") (pin "2") (pinfunction "LED1_2") (pintype "bidirectional"))
    )
    (net (code "157") (name "Net-(U15-LED2)") (class "Default")
      (node (ref "R112") (pin "2") (pinfunction "2_2") (pintype "passive"))
      (node (ref "U15") (pin "3") (pinfunction "LED2_3") (pintype "bidirectional"))
    )
    (net (code "158") (name "Net-(U16-G)") (class "Default")
      (node (ref "U16") (pin "1") (pinfunction "G_1") (pintype "bidirectional"))
      (node (ref "U19") (pin "7") (pinfunction "1Y_7") (pintype "bidirectional"))
    )
    (net (code "159") (name "Net-(U17-G)") (class "Default")
      (node (ref "U17") (pin "1") (pinfunction "G_1") (pintype "bidirectional"))
      (node (ref "U19") (pin "5") (pinfunction "2Y_5") (pintype "bidirectional"))
    )
    (net (code "160") (name "Net-(U18-G)") (class "Default")
      (node (ref "U18") (pin "1") (pinfunction "G_1") (pintype "bidirectional"))
      (node (ref "U19") (pin "2") (pinfunction "3Y_2") (pintype "bidirectional"))
    )
    (net (code "161") (name "Net-(U19-1A)") (class "Default")
      (node (ref "R110") (pin "1") (pinfunction "1_1") (pintype "passive"))
      (node (ref "R113") (pin "2") (pinfunction "2_2") (pintype "passive"))
      (node (ref "U19") (pin "1") (pinfunction "1A_1") (pintype "bidirectional"))
    )
    (net (code "162") (name "Net-(U19-2A)") (class "Default")
      (node (ref "R111") (pin "1") (pinfunction "1_1") (pintype "passive"))
      (node (ref "R114") (pin "2") (pinfunction "2_2") (pintype "passive"))
      (node (ref "U19") (pin "3") (pinfunction "2A_3") (pintype "bidirectional"))
    )
    (net (code "163") (name "Net-(U19-3A)") (class "Default")
      (node (ref "R112") (pin "1") (pinfunction "1_1") (pintype "passive"))
      (node (ref "R115") (pin "2") (pinfunction "2_2") (pintype "passive"))
      (node (ref "U19") (pin "6") (pinfunction "3A_6") (pintype "bidirectional"))
    )
    (net (code "164") (name "POTS-SCL") (class "Default")
      (node (ref "POTS-SCL") (pin "TP") (pinfunction "TP_TP") (pintype "input"))
      (node (ref "U10") (pin "3") (pinfunction "SCL_3") (pintype "bidirectional"))
      (node (ref "U11") (pin "3") (pinfunction "SCL_3") (pintype "bidirectional"))
      (node (ref "U12") (pin "3") (pinfunction "SCL_3") (pintype "bidirectional"))
      (node (ref "U4") (pin "68") (pinfunction "PJ5(PCINT14)_68") (pintype "bidirectional"))
      (node (ref "U8") (pin "3") (pinfunction "SCL_3") (pintype "bidirectional"))
      (node (ref "U9") (pin "3") (pinfunction "SCL_3") (pintype "bidirectional"))
    )
    (net (code "165") (name "RX-LED") (class "Default")
      (node (ref "RX") (pin "C") (pinfunction "C_C") (pintype "passive"))
      (node (ref "U3") (pin "10") (pinfunction "(INT5/AIN3)PD4_10") (pintype "bidirectional"))
    )
    (net (code "166") (name "SCL") (class "Default")
      (node (ref "I2C") (pin "4") (pinfunction "4_4") (pintype "passive"))
      (node (ref "R78") (pin "1") (pinfunction "1_1") (pintype "passive"))
      (node (ref "U15") (pin "6") (pinfunction "SCL_6") (pintype "bidirectional"))
      (node (ref "U4") (pin "43") (pinfunction "(SCL/INT0)PD0_43") (pintype "bidirectional"))
    )
    (net (code "167") (name "SD-CD") (class "Default")
      (node (ref "INTERFACE") (pin "16") (pinfunction "16_16") (pintype "passive"))
      (node (ref "U4") (pin "18") (pinfunction "PH6(OC2B)_18") (pintype "bidirectional"))
    )
    (net (code "168") (name "SD-CS") (class "Default")
      (node (ref "INTERFACE") (pin "17") (pinfunction "17_17") (pintype "passive"))
      (node (ref "U4") (pin "19") (pinfunction "(SS/PCINT0)PB0_19") (pintype "bidirectional"))
    )
    (net (code "169") (name "SD-WP") (class "Default")
      (node (ref "INTERFACE") (pin "15") (pinfunction "15_15") (pintype "passive"))
      (node (ref "U4") (pin "17") (pinfunction "PH5(OC4C)_17") (pintype "bidirectional"))
    )
    (net (code "170") (name "SDA") (class "Default")
      (node (ref "I2C") (pin "3") (pinfunction "3_3") (pintype "passive"))
      (node (ref "R77") (pin "1") (pinfunction "1_1") (pintype "passive"))
      (node (ref "U15") (pin "7") (pinfunction "SDA_7") (pintype "bidirectional"))
      (node (ref "U4") (pin "44") (pinfunction "(SDA/INT1)PD1_44") (pintype "bidirectional"))
    )
    (net (code "171") (name "TEMP1") (class "Default")
      (node (ref "C9") (pin "2") (pinfunction "2_2") (pintype "passive"))
      (node (ref "R53") (pin "1") (pinfunction "1_1") (pintype "passive"))
      (node (ref "TEMP1") (pin "1") (pinfunction "1_1") (pintype "passive"))
      (node (ref "U4") (pin "84") (pinfunction "PK5(ADC13/PCINT21)_84") (pintype "bidirectional"))
    )
    (net (code "172") (name "TEMP2") (class "Default")
      (node (ref "C8") (pin "2") (pinfunction "2_2") (pintype "passive"))
      (node (ref "R48") (pin "1") (pinfunction "1_1") (pintype "passive"))
      (node (ref "TEMP2") (pin "1") (pinfunction "1_1") (pintype "passive"))
      (node (ref "U4") (pin "85") (pinfunction "PK4(ADC12/PCINT20)_85") (pintype "bidirectional"))
    )
    (net (code "173") (name "TX-LED") (class "Default")
      (node (ref "TX") (pin "C") (pinfunction "C_C") (pintype "passive"))
      (node (ref "U3") (pin "11") (pinfunction "(XCK/AIN4/PCINT12)PD5_11") (pintype "bidirectional"))
    )
    (net (code "174") (name "UGND") (class "Default")
      (node (ref "C17") (pin "1") (pinfunction "1_1") (pintype "passive"))
      (node (ref "L1") (pin "1") (pinfunction "1_1") (pintype "passive"))
      (node (ref "R67") (pin "1") (pinfunction "1_1") (pintype "passive"))
      (node (ref "U3") (pin "28") (pinfunction "UGND_28") (pintype "power_in"))
      (node (ref "UGND") (pin "TP") (pinfunction "TP_TP") (pintype "input"))
      (node (ref "X2") (pin "4") (pinfunction "4_4") (pintype "bidirectional"))
    )
    (net (code "175") (name "UVCC") (class "Default")
      (node (ref "C24") (pin "2") (pinfunction "2_2") (pintype "passive"))
      (node (ref "U3") (pin "31") (pinfunction "UVCC_31") (pintype "power_in"))
      (node (ref "UVCC") (pin "TP") (pinfunction "TP_TP") (pintype "input"))
      (node (ref "X2") (pin "1") (pinfunction "1_1") (pintype "bidirectional"))
    )
    (net (code "176") (name "X-AXIS-DIR") (class "Default")
      (node (ref "BOTSTEP-X") (pin "16") (pinfunction "DIR_16") (pintype "input"))
      (node (ref "U4") (pin "97") (pinfunction "(ADC0)PF0_97") (pintype "bidirectional"))
      (node (ref "X-DIR") (pin "TP") (pinfunction "TP_TP") (pintype "input"))
    )
    (net (code "177") (name "X-AXIS-EN") (class "Default")
      (node (ref "BOTSTEP-X") (pin "9") (pinfunction "EN_9") (pintype "input"))
      (node (ref "R39") (pin "1") (pinfunction "1_1") (pintype "passive"))
      (node (ref "U4") (pin "95") (pinfunction "(ADC2)PF2_95") (pintype "bidirectional"))
      (node (ref "X-EN") (pin "TP") (pinfunction "TP_TP") (pintype "input"))
    )
    (net (code "178") (name "X-AXIS-POT") (class "Default")
      (node (ref "R103") (pin "2") (pinfunction "2_2") (pintype "passive"))
      (node (ref "U4") (pin "94") (pinfunction "(ADC3)PF3_94") (pintype "bidirectional"))
    )
    (net (code "179") (name "X-AXIS-STEP") (class "Default")
      (node (ref "BOTSTEP-X") (pin "15") (pinfunction "STEP_15") (pintype "input"))
      (node (ref "U4") (pin "96") (pinfunction "(ADC1)PF1_96") (pintype "bidirectional"))
      (node (ref "X-STEP") (pin "TP") (pinfunction "TP_TP") (pintype "input"))
    )
    (net (code "180") (name "X-MAX") (class "Default")
      (node (ref "TP29") (pin "TP") (pinfunction "TP_TP") (pintype "input"))
      (node (ref "U4") (pin "36") (pinfunction "PL1(ICP5)_36") (pintype "bidirectional"))
      (node (ref "X-MAX") (pin "4") (pinfunction "S_4") (pintype "passive"))
    )
    (net (code "181") (name "X-MIN") (class "Default")
      (node (ref "TP28") (pin "TP") (pinfunction "TP_TP") (pintype "input"))
      (node (ref "U4") (pin "35") (pinfunction "PL0(ICP4)_35") (pintype "bidirectional"))
      (node (ref "X-MIN") (pin "4") (pinfunction "S_4") (pintype "passive"))
    )
    (net (code "182") (name "Y-AXIS-DIR") (class "Default")
      (node (ref "BOTSTEP-Y") (pin "16") (pinfunction "DIR_16") (pintype "input"))
      (node (ref "U4") (pin "93") (pinfunction "(ADC4/TCK)PF4_93") (pintype "bidirectional"))
      (node (ref "Y-DIR") (pin "TP") (pinfunction "TP_TP") (pintype "input"))
    )
    (net (code "183") (name "Y-AXIS-EN") (class "Default")
      (node (ref "BOTSTEP-Y") (pin "9") (pinfunction "EN_9") (pintype "input"))
      (node (ref "R40") (pin "1") (pinfunction "1_1") (pintype "passive"))
      (node (ref "U4") (pin "91") (pinfunction "(ADC6/TDO)PF6_91") (pintype "bidirectional"))
      (node (ref "Y-EN") (pin "TP") (pinfunction "TP_TP") (pintype "input"))
    )
    (net (code "184") (name "Y-AXIS-POT") (class "Default")
      (node (ref "R104") (pin "2") (pinfunction "2_2") (pintype "passive"))
      (node (ref "U4") (pin "90") (pinfunction "(ADC7/TDI)PF7_90") (pintype "bidirectional"))
    )
    (net (code "185") (name "Y-AXIS-STEP") (class "Default")
      (node (ref "BOTSTEP-Y") (pin "15") (pinfunction "STEP_15") (pintype "input"))
      (node (ref "U4") (pin "92") (pinfunction "(ADC5/TMS)PF5_92") (pintype "bidirectional"))
      (node (ref "Y-STEP") (pin "TP") (pinfunction "TP_TP") (pintype "input"))
    )
    (net (code "186") (name "Y-MAX") (class "Default")
      (node (ref "TP31") (pin "TP") (pinfunction "TP_TP") (pintype "input"))
      (node (ref "U4") (pin "38") (pinfunction "PL3(OC5A)_38") (pintype "bidirectional"))
      (node (ref "Y-MAX") (pin "4") (pinfunction "S_4") (pintype "passive"))
    )
    (net (code "187") (name "Y-MIN") (class "Default")
      (node (ref "TP30") (pin "TP") (pinfunction "TP_TP") (pintype "input"))
      (node (ref "U4") (pin "37") (pinfunction "PL2(T5)_37") (pintype "bidirectional"))
      (node (ref "Y-MIN") (pin "4") (pinfunction "S_4") (pintype "passive"))
    )
    (net (code "188") (name "Z-AXIS-DIR") (class "Default")
      (node (ref "BOTSTEP-Z") (pin "16") (pinfunction "DIR_16") (pintype "input"))
      (node (ref "U4") (pin "89") (pinfunction "PK0(ADC8/PCINT16)_89") (pintype "bidirectional"))
      (node (ref "Z-DIR") (pin "TP") (pinfunction "TP_TP") (pintype "input"))
    )
    (net (code "189") (name "Z-AXIS-EN") (class "Default")
      (node (ref "BOTSTEP-Z") (pin "9") (pinfunction "EN_9") (pintype "input"))
      (node (ref "R41") (pin "1") (pinfunction "1_1") (pintype "passive"))
      (node (ref "U4") (pin "87") (pinfunction "PK2(ADC10/PCINT18)_87") (pintype "bidirectional"))
      (node (ref "Z-EN") (pin "TP") (pinfunction "TP_TP") (pintype "input"))
    )
    (net (code "190") (name "Z-AXIS-POT") (class "Default")
      (node (ref "R105") (pin "2") (pinfunction "2_2") (pintype "passive"))
      (node (ref "U4") (pin "86") (pinfunction "PK3(ADC11/PCINT19)_86") (pintype "bidirectional"))
    )
    (net (code "191") (name "Z-AXIS-STEP") (class "Default")
      (node (ref "BOTSTEP-Z") (pin "15") (pinfunction "STEP_15") (pintype "input"))
      (node (ref "U4") (pin "88") (pinfunction "PK1(ADC9/PCINT17)_88") (pintype "bidirectional"))
      (node (ref "Z-STEP") (pin "TP") (pinfunction "TP_TP") (pintype "input"))
    )
    (net (code "192") (name "Z-MAX") (class "Default")
      (node (ref "TP33") (pin "TP") (pinfunction "TP_TP") (pintype "input"))
      (node (ref "U4") (pin "42") (pinfunction "PL7_42") (pintype "bidirectional"))
      (node (ref "Z-MAX") (pin "4") (pinfunction "S_4") (pintype "passive"))
    )
    (net (code "193") (name "Z-MIN") (class "Default")
      (node (ref "TP32") (pin "TP") (pinfunction "TP_TP") (pintype "input"))
      (node (ref "U4") (pin "41") (pinfunction "PL6_41") (pintype "bidirectional"))
      (node (ref "Z-MIN") (pin "4") (pinfunction "S_4") (pintype "passive"))
    )
    (net (code "194") (name "unconnected-(S1-P1-Pad4)") (class "Default")
      (node (ref "S1") (pin "4") (pinfunction "P1_4") (pintype "passive"))
    )
    (net (code "195") (name "unconnected-(S1-S1-Pad2)") (class "Default")
      (node (ref "S1") (pin "2") (pinfunction "S1_2") (pintype "passive"))
    )
    (net (code "196") (name "unconnected-(U3-(AIN0{slash}INT1)PD1-Pad7)") (class "Default")
      (node (ref "U3") (pin "7") (pinfunction "(AIN0/INT1)PD1_7") (pintype "bidirectional"))
    )
    (net (code "197") (name "unconnected-(U3-(AIN2{slash}PCINT11)PC2-Pad5)") (class "Default")
      (node (ref "U3") (pin "5") (pinfunction "(AIN2/PCINT11)PC2_5") (pintype "bidirectional"))
    )
    (net (code "198") (name "unconnected-(U3-(INT4{slash}ICP1{slash}CLK0)PC7-Pad22)") (class "Default")
      (node (ref "U3") (pin "22") (pinfunction "(INT4/ICP1/CLK0)PC7_22") (pintype "bidirectional"))
    )
    (net (code "199") (name "unconnected-(U3-(OC0B{slash}INT0)PD0-Pad6)") (class "Default")
      (node (ref "U3") (pin "6") (pinfunction "(OC0B/INT0)PD0_6") (pintype "bidirectional"))
    )
    (net (code "200") (name "unconnected-(U3-(OC1A{slash}PCINT8)PC6-Pad23)") (class "Default")
      (node (ref "U3") (pin "23") (pinfunction "(OC1A/PCINT8)PC6_23") (pintype "bidirectional"))
    )
    (net (code "201") (name "unconnected-(U3-(PCINT5)PB5-Pad19)") (class "Default")
      (node (ref "U3") (pin "19") (pinfunction "(PCINT5)PB5_19") (pintype "bidirectional"))
    )
    (net (code "202") (name "unconnected-(U3-(PCINT9{slash}OC1B)PC5-Pad25)") (class "Default")
      (node (ref "U3") (pin "25") (pinfunction "(PCINT9/OC1B)PC5_25") (pintype "bidirectional"))
    )
    (net (code "203") (name "unconnected-(U3-(PCINT10)PC4-Pad26)") (class "Default")
      (node (ref "U3") (pin "26") (pinfunction "(PCINT10)PC4_26") (pintype "bidirectional"))
    )
    (net (code "204") (name "unconnected-(U3-(RTS{slash}AIN5{slash}INT6)PD6-Pad12)") (class "Default")
      (node (ref "U3") (pin "12") (pinfunction "(RTS/AIN5/INT6)PD6_12") (pintype "bidirectional"))
    )
    (net (code "205") (name "unconnected-(U3-(SS{slash}PCINT0)PB0-Pad14)") (class "Default")
      (node (ref "U3") (pin "14") (pinfunction "(SS/PCINT0)PB0_14") (pintype "bidirectional"))
    )
    (net (code "206") (name "unconnected-(U3-(T1{slash}PCINT4)PB4-Pad18)") (class "Default")
      (node (ref "U3") (pin "18") (pinfunction "(T1/PCINT4)PB4_18") (pintype "bidirectional"))
    )
    (net (code "207") (name "unconnected-(U4-(CLKO{slash}ICP3{slash}INT7)PE7-Pad9)") (class "Default")
      (node (ref "U4") (pin "9") (pinfunction "(CLKO/ICP3/INT7)PE7_9") (pintype "bidirectional"))
    )
    (net (code "208") (name "unconnected-(U4-(ICP1)PD4-Pad47)") (class "Default")
      (node (ref "U4") (pin "47") (pinfunction "(ICP1)PD4_47") (pintype "bidirectional"))
    )
    (net (code "209") (name "unconnected-(U4-(OC3A{slash}AIN1)PE3-Pad5)") (class "Default")
      (node (ref "U4") (pin "5") (pinfunction "(OC3A/AIN1)PE3_5") (pintype "bidirectional"))
    )
    (net (code "210") (name "unconnected-(U4-(OC3B{slash}INT4)PE4-Pad6)") (class "Default")
      (node (ref "U4") (pin "6") (pinfunction "(OC3B/INT4)PE4_6") (pintype "bidirectional"))
    )
    (net (code "211") (name "unconnected-(U4-(OC3C{slash}INT5)PE5-Pad7)") (class "Default")
      (node (ref "U4") (pin "7") (pinfunction "(OC3C/INT5)PE5_7") (pintype "bidirectional"))
    )
    (net (code "212") (name "unconnected-(U4-(T1)PD6-Pad49)") (class "Default")
      (node (ref "U4") (pin "49") (pinfunction "(T1)PD6_49") (pintype "bidirectional"))
    )
    (net (code "213") (name "unconnected-(U4-(T3{slash}INT6)PE6-Pad8)") (class "Default")
      (node (ref "U4") (pin "8") (pinfunction "(T3/INT6)PE6_8") (pintype "bidirectional"))
    )
    (net (code "214") (name "unconnected-(U4-(TOSC2)PG3-Pad28)") (class "Default")
      (node (ref "U4") (pin "28") (pinfunction "(TOSC2)PG3_28") (pintype "bidirectional"))
    )
    (net (code "215") (name "unconnected-(U4-(XCK0{slash}AIN0)PE2-Pad4)") (class "Default")
      (node (ref "U4") (pin "4") (pinfunction "(XCK0/AIN0)PE2_4") (pintype "bidirectional"))
    )
    (net (code "216") (name "unconnected-(U4-(XCK1)PD5-Pad48)") (class "Default")
      (node (ref "U4") (pin "48") (pinfunction "(XCK1)PD5_48") (pintype "bidirectional"))
    )
    (net (code "217") (name "unconnected-(U4-PH7(T4)-Pad27)") (class "Default")
      (node (ref "U4") (pin "27") (pinfunction "PH7(T4)_27") (pintype "bidirectional"))
    )
    (net (code "218") (name "unconnected-(U4-PJ7-Pad79)") (class "Default")
      (node (ref "U4") (pin "79") (pinfunction "PJ7_79") (pintype "bidirectional"))
    )
    (net (code "219") (name "unconnected-(U6-NC-Pad3)") (class "Default")
      (node (ref "U6") (pin "3") (pinfunction "NC_3") (pintype "bidirectional"))
    )
    (net (code "220") (name "unconnected-(U7-NC-Pad3)") (class "Default")
      (node (ref "U7") (pin "3") (pinfunction "NC_3") (pintype "bidirectional"))
    )
    (net (code "221") (name "unconnected-(U15-LED3-Pad5)") (class "Default")
      (node (ref "U15") (pin "5") (pinfunction "LED3_5") (pintype "bidirectional"))
    )
    (net (code "222") (name "unconnected-(X3-Pad3)") (class "Default")
      (node (ref "X3") (pin "3") (pinfunction "3_3") (pintype "passive"))
    )
    (net (code "223") (name "unconnected-(X3-Pad15)") (class "Default")
      (node (ref "X3") (pin "15") (pinfunction "15_15") (pintype "passive"))
    )
    (net (code "224") (name "unconnected-(X3-Pad16)") (class "Default")
      (node (ref "X3") (pin "16") (pinfunction "16_16") (pintype "passive"))
    )
    (net (code "225") (name "unconnected-(X3-Pad17)") (class "Default")
      (node (ref "X3") (pin "17") (pinfunction "17_17") (pintype "passive"))
    )
  )
)
